# 51_VO-HDMI2_0_TX_DP_to_HDMI.net
KiCad netlist of a schematic drawn in Altium Designer
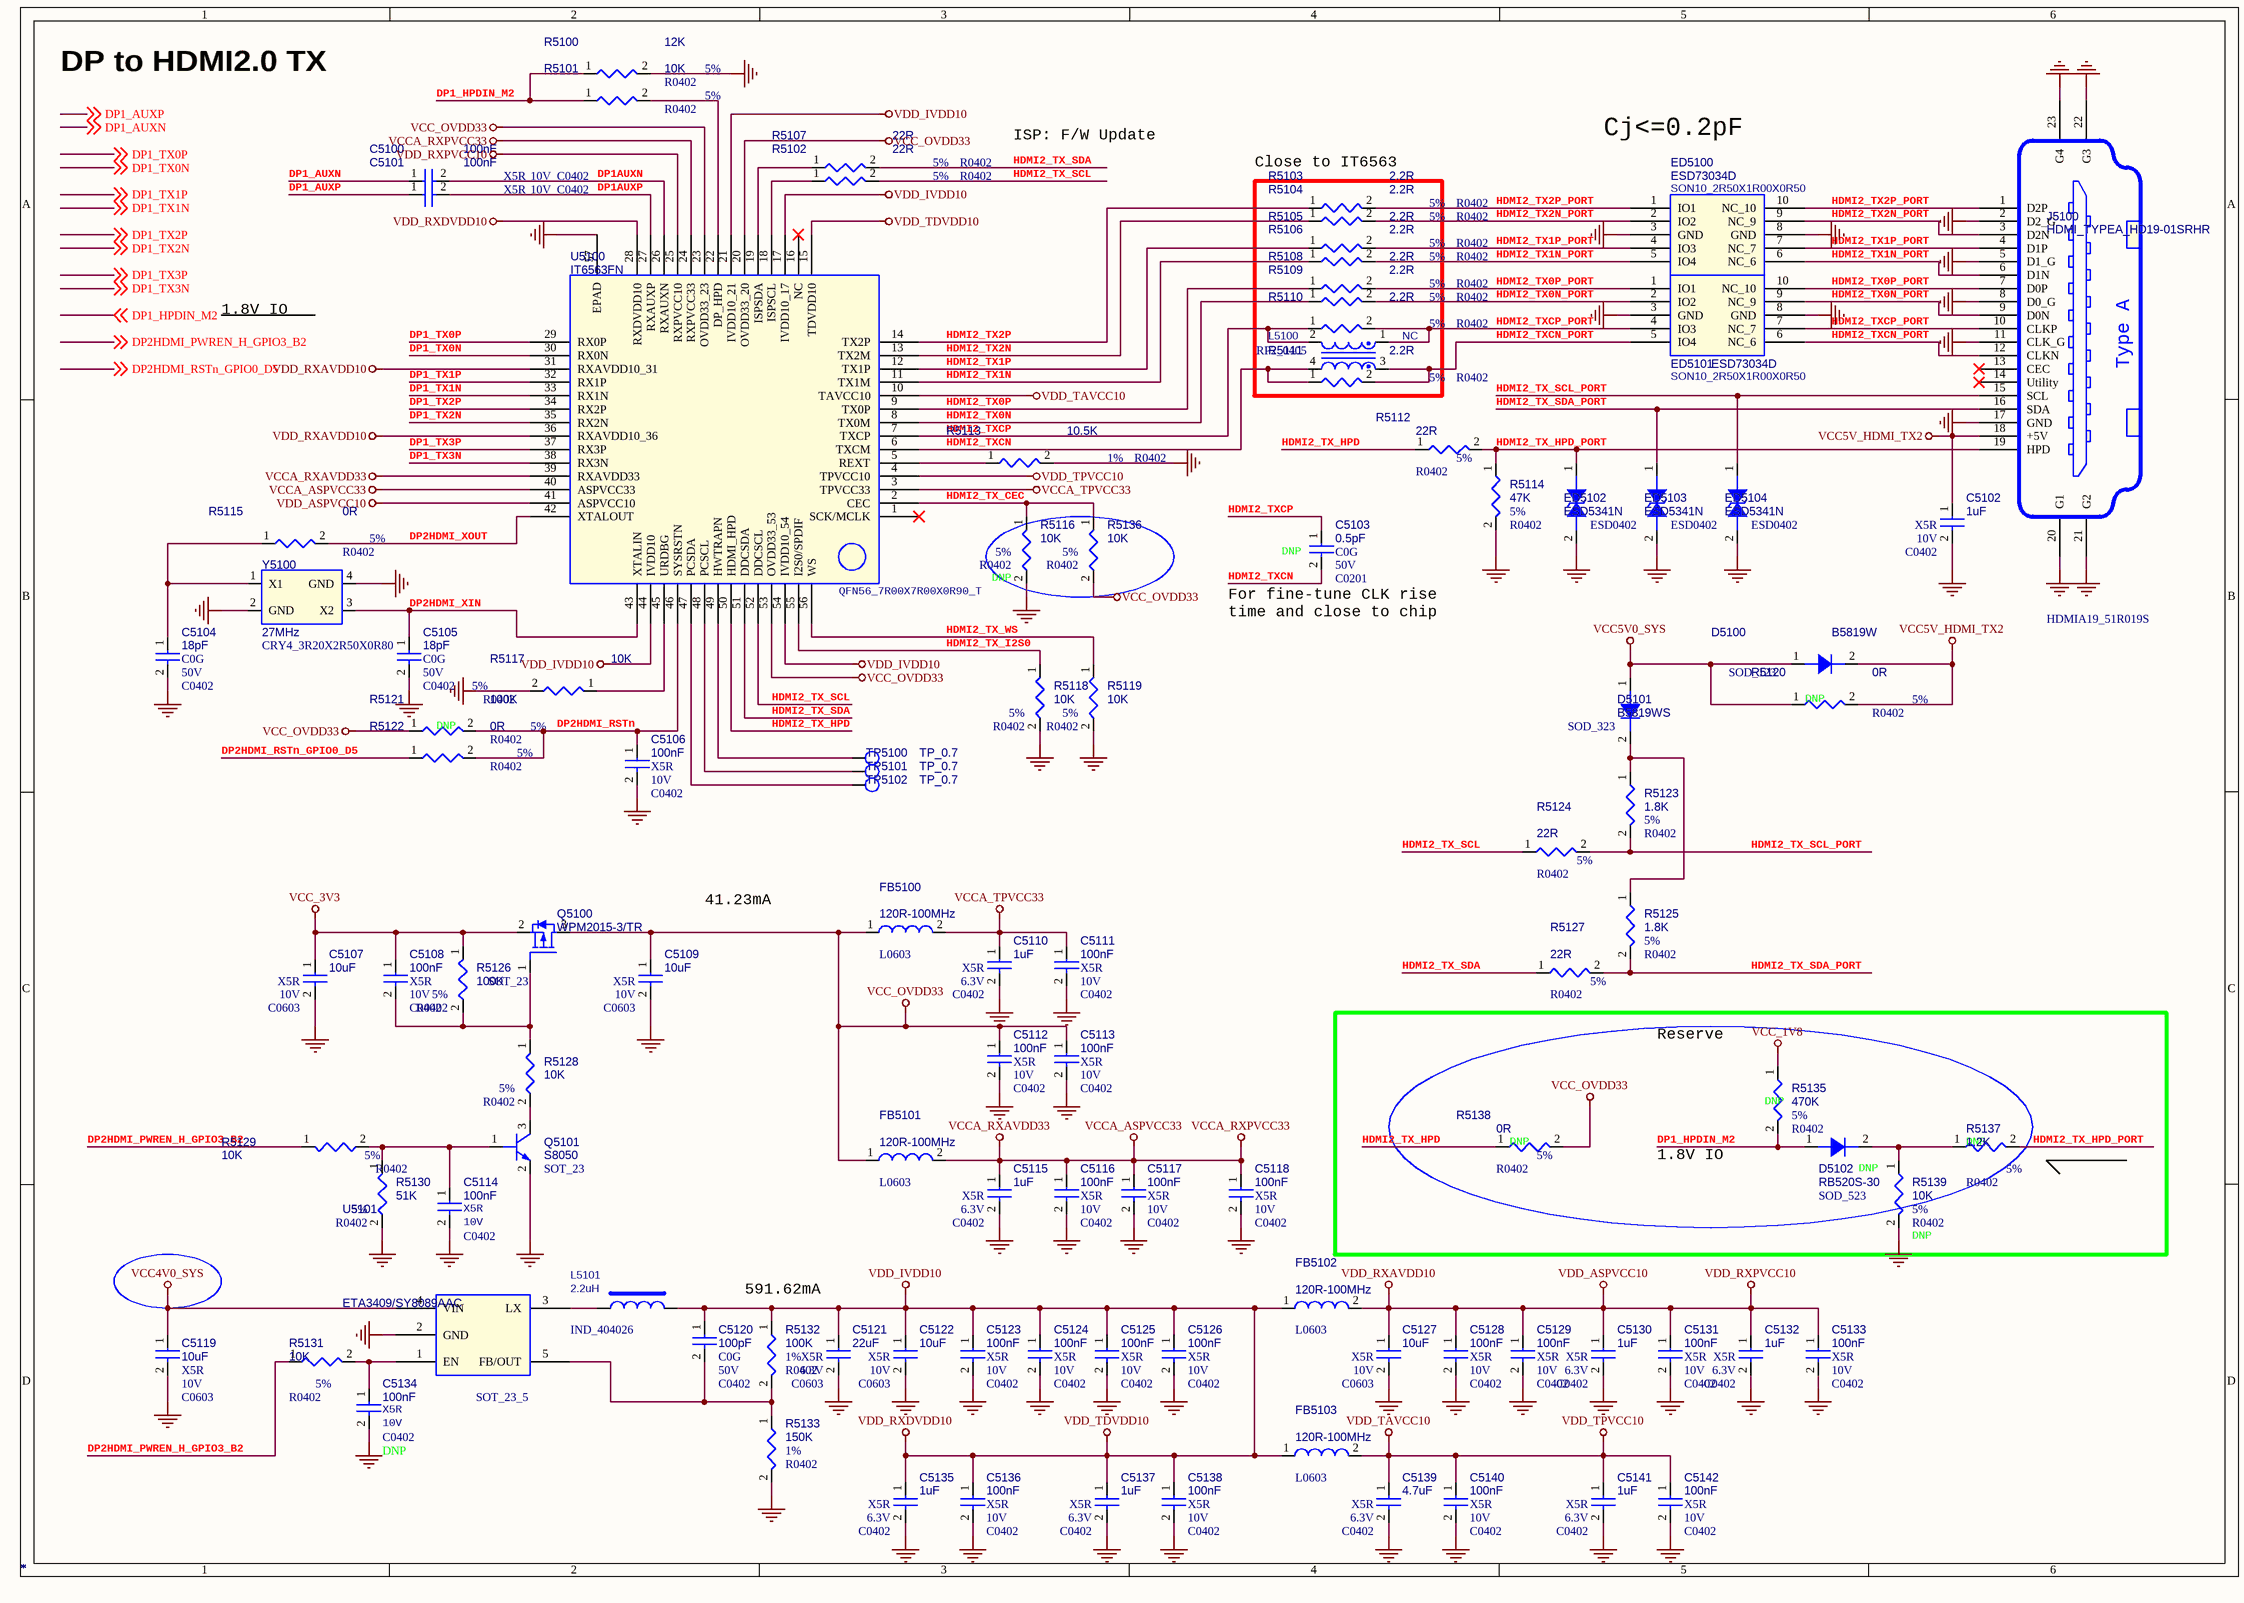
[diagram p0: 51.VO-HDMI2.0 TX(DP to HDMI).SchDoc]

(export (version "E")
  (design (tool "Eeschema 10.0.6"))
  (components
    (comp (ref "C5100")
      (value "*")
      (footprint "C0402")
      (description "cap,100.00nF,+/-10%,10V,X5R,C0402")
      (fields
        (field (name "VOLTAGE") "10V")
        (field (name "PCB FOOTPRINT") "C0402")
        (field (name "DIELECTRIC") "X5R")
        (field (name "TOLERANCE") "10%")
        (field (name "MANUFACTURER") "TDK")
        (field (name "ALTIUM_UNNAMED_1") "100nF")
        (field (name "CREATED BY") "JJJ")
      )
      (libsource (lib "*") (part "CAP NP"))
    )
    (comp (ref "C5101")
      (value "*")
      (footprint "C0402")
      (description "cap,100.00nF,+/-10%,10V,X5R,C0402")
      (fields
        (field (name "VOLTAGE") "10V")
        (field (name "PCB FOOTPRINT") "C0402")
        (field (name "DIELECTRIC") "X5R")
        (field (name "MANUFACTURER") "TDK")
        (field (name "TOLERANCE") "10%")
        (field (name "ALTIUM_UNNAMED_1") "100nF")
        (field (name "CREATED BY") "JJJ")
      )
      (libsource (lib "*") (part "CAP NP"))
    )
    (comp (ref "C5102")
      (value "*")
      (footprint "C0402")
      (description "cap,1.00uF,+/-10%,10V,X5R,C0402")
      (fields
        (field (name "VOLTAGE") "10V")
        (field (name "PCB FOOTPRINT") "C0402")
        (field (name "DIELECTRIC") "X5R")
        (field (name "MANUFACTURER") "TDK")
        (field (name "TOLERANCE") "10%")
        (field (name "ALTIUM_UNNAMED_1") "1uF")
        (field (name "CREATED BY") "JJJ")
      )
      (libsource (lib "*") (part "CAP NP"))
    )
    (comp (ref "C5103")
      (value "*")
      (footprint "C0201")
      (description "cap,0.50pF,+/-0.25,50V,C0G,C0201")
      (fields
        (field (name "VOLTAGE") "50V")
        (field (name "PCB FOOTPRINT") "C0201")
        (field (name "DIELECTRIC") "C0G")
        (field (name "OPTION") "DNP")
        (field (name "TOLERANCE") "+/-0.25pF")
        (field (name "MANUFACTURER") "TDK")
        (field (name "ALTIUM_UNNAMED_1") "0.5pF")
        (field (name "CREATED BY") "JJJ")
      )
      (libsource (lib "*") (part "CAP NP"))
    )
    (comp (ref "C5104")
      (value "*")
      (footprint "C0402")
      (description "cap,18.00pF,+/-5%,50V,C0G,C0402")
      (fields
        (field (name "VOLTAGE") "50V")
        (field (name "PCB FOOTPRINT") "C0402")
        (field (name "DIELECTRIC") "C0G")
        (field (name "MANUFACTURER") "TDK")
        (field (name "TOLERANCE") "5%")
        (field (name "ALTIUM_UNNAMED_1") "18pF")
        (field (name "CREATED BY") "JJJ")
      )
      (libsource (lib "*") (part "CAP NP"))
    )
    (comp (ref "C5105")
      (value "*")
      (footprint "C0402")
      (description "cap,18.00pF,+/-5%,50V,C0G,C0402")
      (fields
        (field (name "VOLTAGE") "50V")
        (field (name "PCB FOOTPRINT") "C0402")
        (field (name "DIELECTRIC") "C0G")
        (field (name "MANUFACTURER") "TDK")
        (field (name "TOLERANCE") "5%")
        (field (name "ALTIUM_UNNAMED_1") "18pF")
        (field (name "CREATED BY") "JJJ")
      )
      (libsource (lib "*") (part "CAP NP"))
    )
    (comp (ref "C5106")
      (value "*")
      (footprint "C0402")
      (description "cap,100.00nF,+/-10%,10V,X5R,C0402")
      (fields
        (field (name "VOLTAGE") "10V")
        (field (name "PCB FOOTPRINT") "C0402")
        (field (name "DIELECTRIC") "X5R")
        (field (name "MANUFACTURER") "TDK")
        (field (name "TOLERANCE") "10%")
        (field (name "ALTIUM_UNNAMED_1") "100nF")
        (field (name "CREATED BY") "JJJ")
      )
      (libsource (lib "*") (part "CAP NP"))
    )
    (comp (ref "C5107")
      (value "*")
      (footprint "C0603")
      (description "cap,10.00uF,+/-10%,10V,X5R,C0603")
      (fields
        (field (name "VOLTAGE") "10V")
        (field (name "PCB FOOTPRINT") "C0603")
        (field (name "DIELECTRIC") "X5R")
        (field (name "MANUFACTURER") "TDK")
        (field (name "TOLERANCE") "10%")
        (field (name "ALTIUM_UNNAMED_1") "10uF")
        (field (name "CREATED BY") "JJJ")
      )
      (libsource (lib "*") (part "CAP NP"))
    )
    (comp (ref "C5108")
      (value "*")
      (footprint "C0402")
      (description "cap,100.00nF,+/-10%,10V,X5R,C0402")
      (fields
        (field (name "VOLTAGE") "10V")
        (field (name "PCB FOOTPRINT") "C0402")
        (field (name "DIELECTRIC") "X5R")
        (field (name "TOLERANCE") "10%")
        (field (name "MANUFACTURER") "TDK")
        (field (name "ALTIUM_UNNAMED_1") "100nF")
        (field (name "CREATED BY") "JJJ")
      )
      (libsource (lib "*") (part "CAP NP"))
    )
    (comp (ref "C5109")
      (value "*")
      (footprint "C0603")
      (description "cap,10.00uF,+/-10%,10V,X5R,C0603")
      (fields
        (field (name "VOLTAGE") "10V")
        (field (name "PCB FOOTPRINT") "C0603")
        (field (name "DIELECTRIC") "X5R")
        (field (name "MANUFACTURER") "TDK")
        (field (name "TOLERANCE") "10%")
        (field (name "ALTIUM_UNNAMED_1") "10uF")
        (field (name "CREATED BY") "JJJ")
      )
      (libsource (lib "*") (part "CAP NP"))
    )
    (comp (ref "C5110")
      (value "*")
      (footprint "C0402")
      (description "cap,1.00uF,+/-10%,6.3V,X5R,C0402")
      (fields
        (field (name "VOLTAGE") "6.3V")
        (field (name "PCB FOOTPRINT") "C0402")
        (field (name "DIELECTRIC") "X5R")
        (field (name "TOLERANCE") "10%")
        (field (name "MANUFACTURER") "TDK")
        (field (name "ALTIUM_UNNAMED_1") "1uF")
        (field (name "CREATED BY") "JJJ")
      )
      (libsource (lib "*") (part "CAP NP"))
    )
    (comp (ref "C5111")
      (value "*")
      (footprint "C0402")
      (description "cap,100.00nF,+/-10%,10V,X5R,C0402")
      (fields
        (field (name "VOLTAGE") "10V")
        (field (name "PCB FOOTPRINT") "C0402")
        (field (name "DIELECTRIC") "X5R")
        (field (name "TOLERANCE") "10%")
        (field (name "MANUFACTURER") "TDK")
        (field (name "ALTIUM_UNNAMED_1") "100nF")
        (field (name "CREATED BY") "JJJ")
      )
      (libsource (lib "*") (part "CAP NP"))
    )
    (comp (ref "C5112")
      (value "*")
      (footprint "C0402")
      (description "cap,100.00nF,+/-10%,10V,X5R,C0402")
      (fields
        (field (name "VOLTAGE") "10V")
        (field (name "PCB FOOTPRINT") "C0402")
        (field (name "DIELECTRIC") "X5R")
        (field (name "MANUFACTURER") "TDK")
        (field (name "TOLERANCE") "10%")
        (field (name "ALTIUM_UNNAMED_1") "100nF")
        (field (name "CREATED BY") "JJJ")
      )
      (libsource (lib "*") (part "CAP NP"))
    )
    (comp (ref "C5113")
      (value "*")
      (footprint "C0402")
      (description "cap,100.00nF,+/-10%,10V,X5R,C0402")
      (fields
        (field (name "VOLTAGE") "10V")
        (field (name "PCB FOOTPRINT") "C0402")
        (field (name "DIELECTRIC") "X5R")
        (field (name "MANUFACTURER") "TDK")
        (field (name "TOLERANCE") "10%")
        (field (name "ALTIUM_UNNAMED_1") "100nF")
        (field (name "CREATED BY") "JJJ")
      )
      (libsource (lib "*") (part "CAP NP"))
    )
    (comp (ref "C5114")
      (value "*")
      (footprint "C0402")
      (description "cap,100.00nF,+/-10%,10V,X5R,C0402")
      (fields
        (field (name "VOLTAGE") "10V")
        (field (name "PCB FOOTPRINT") "C0402")
        (field (name "DIELECTRIC") "X5R")
        (field (name "TOLERANCE") "10%")
        (field (name "MANUFACTURER") "TDK")
        (field (name "ALTIUM_UNNAMED_1") "100nF")
        (field (name "CREATED BY") "JJJ")
      )
      (libsource (lib "*") (part "CAP NP"))
    )
    (comp (ref "C5115")
      (value "*")
      (footprint "C0402")
      (description "cap,1.00uF,+/-10%,6.3V,X5R,C0402")
      (fields
        (field (name "VOLTAGE") "6.3V")
        (field (name "PCB FOOTPRINT") "C0402")
        (field (name "DIELECTRIC") "X5R")
        (field (name "TOLERANCE") "10%")
        (field (name "MANUFACTURER") "TDK")
        (field (name "ALTIUM_UNNAMED_1") "1uF")
        (field (name "CREATED BY") "JJJ")
      )
      (libsource (lib "*") (part "CAP NP"))
    )
    (comp (ref "C5116")
      (value "*")
      (footprint "C0402")
      (description "cap,100.00nF,+/-10%,10V,X5R,C0402")
      (fields
        (field (name "VOLTAGE") "10V")
        (field (name "PCB FOOTPRINT") "C0402")
        (field (name "DIELECTRIC") "X5R")
        (field (name "TOLERANCE") "10%")
        (field (name "MANUFACTURER") "TDK")
        (field (name "ALTIUM_UNNAMED_1") "100nF")
        (field (name "CREATED BY") "JJJ")
      )
      (libsource (lib "*") (part "CAP NP"))
    )
    (comp (ref "C5117")
      (value "*")
      (footprint "C0402")
      (description "cap,100.00nF,+/-10%,10V,X5R,C0402")
      (fields
        (field (name "VOLTAGE") "10V")
        (field (name "PCB FOOTPRINT") "C0402")
        (field (name "DIELECTRIC") "X5R")
        (field (name "MANUFACTURER") "TDK")
        (field (name "TOLERANCE") "10%")
        (field (name "ALTIUM_UNNAMED_1") "100nF")
        (field (name "CREATED BY") "JJJ")
      )
      (libsource (lib "*") (part "CAP NP"))
    )
    (comp (ref "C5118")
      (value "*")
      (footprint "C0402")
      (description "cap,100.00nF,+/-10%,10V,X5R,C0402")
      (fields
        (field (name "VOLTAGE") "10V")
        (field (name "PCB FOOTPRINT") "C0402")
        (field (name "DIELECTRIC") "X5R")
        (field (name "MANUFACTURER") "TDK")
        (field (name "TOLERANCE") "10%")
        (field (name "ALTIUM_UNNAMED_1") "100nF")
        (field (name "CREATED BY") "JJJ")
      )
      (libsource (lib "*") (part "CAP NP"))
    )
    (comp (ref "C5119")
      (value "*")
      (footprint "C0603")
      (description "cap,10.00uF,+/-10%,10V,X5R,C0603")
      (fields
        (field (name "VOLTAGE") "10V")
        (field (name "PCB FOOTPRINT") "C0603")
        (field (name "DIELECTRIC") "X5R")
        (field (name "TOLERANCE") "10%")
        (field (name "MANUFACTURER") "TDK")
        (field (name "ALTIUM_UNNAMED_1") "10uF")
        (field (name "CREATED BY") "JJJ")
      )
      (libsource (lib "*") (part "CAP NP"))
    )
    (comp (ref "C5120")
      (value "*")
      (footprint "C0402")
      (description "cap,100.00pF,+/-10%,50V,C0G,C0402")
      (fields
        (field (name "VOLTAGE") "50V")
        (field (name "PCB FOOTPRINT") "C0402")
        (field (name "DIELECTRIC") "C0G")
        (field (name "TOLERANCE") "10%")
        (field (name "MANUFACTURER") "TDK")
        (field (name "ALTIUM_UNNAMED_1") "100pF")
        (field (name "CREATED BY") "JJJ")
      )
      (libsource (lib "*") (part "CAP NP"))
    )
    (comp (ref "C5121")
      (value "*")
      (footprint "C0603")
      (description "cap,22.00uF,+/-20%,6.3V,X5R,C0603")
      (fields
        (field (name "VOLTAGE") "6.3V")
        (field (name "PCB FOOTPRINT") "C0603")
        (field (name "DIELECTRIC") "X5R")
        (field (name "TOLERANCE") "20%")
        (field (name "MANUFACTURER") "TDK")
        (field (name "ALTIUM_UNNAMED_1") "22uF")
        (field (name "CREATED BY") "JJJ")
      )
      (libsource (lib "*") (part "CAP NP"))
    )
    (comp (ref "C5122")
      (value "*")
      (footprint "C0603")
      (description "cap,10.00uF,+/-10%,10V,X5R,C0603")
      (fields
        (field (name "VOLTAGE") "10V")
        (field (name "PCB FOOTPRINT") "C0603")
        (field (name "DIELECTRIC") "X5R")
        (field (name "MANUFACTURER") "TDK")
        (field (name "TOLERANCE") "10%")
        (field (name "ALTIUM_UNNAMED_1") "10uF")
        (field (name "CREATED BY") "JJJ")
      )
      (libsource (lib "*") (part "CAP NP"))
    )
    (comp (ref "C5123")
      (value "*")
      (footprint "C0402")
      (description "cap,100.00nF,+/-10%,10V,X5R,C0402")
      (fields
        (field (name "VOLTAGE") "10V")
        (field (name "PCB FOOTPRINT") "C0402")
        (field (name "DIELECTRIC") "X5R")
        (field (name "MANUFACTURER") "TDK")
        (field (name "TOLERANCE") "10%")
        (field (name "ALTIUM_UNNAMED_1") "100nF")
        (field (name "CREATED BY") "JJJ")
      )
      (libsource (lib "*") (part "CAP NP"))
    )
    (comp (ref "C5124")
      (value "*")
      (footprint "C0402")
      (description "cap,100.00nF,+/-10%,10V,X5R,C0402")
      (fields
        (field (name "VOLTAGE") "10V")
        (field (name "PCB FOOTPRINT") "C0402")
        (field (name "DIELECTRIC") "X5R")
        (field (name "MANUFACTURER") "TDK")
        (field (name "TOLERANCE") "10%")
        (field (name "ALTIUM_UNNAMED_1") "100nF")
        (field (name "CREATED BY") "JJJ")
      )
      (libsource (lib "*") (part "CAP NP"))
    )
    (comp (ref "C5125")
      (value "*")
      (footprint "C0402")
      (description "cap,100.00nF,+/-10%,10V,X5R,C0402")
      (fields
        (field (name "VOLTAGE") "10V")
        (field (name "PCB FOOTPRINT") "C0402")
        (field (name "DIELECTRIC") "X5R")
        (field (name "TOLERANCE") "10%")
        (field (name "MANUFACTURER") "TDK")
        (field (name "ALTIUM_UNNAMED_1") "100nF")
        (field (name "CREATED BY") "JJJ")
      )
      (libsource (lib "*") (part "CAP NP"))
    )
    (comp (ref "C5126")
      (value "*")
      (footprint "C0402")
      (description "cap,100.00nF,+/-10%,10V,X5R,C0402")
      (fields
        (field (name "VOLTAGE") "10V")
        (field (name "PCB FOOTPRINT") "C0402")
        (field (name "DIELECTRIC") "X5R")
        (field (name "MANUFACTURER") "TDK")
        (field (name "TOLERANCE") "10%")
        (field (name "ALTIUM_UNNAMED_1") "100nF")
        (field (name "CREATED BY") "JJJ")
      )
      (libsource (lib "*") (part "CAP NP"))
    )
    (comp (ref "C5127")
      (value "*")
      (footprint "C0603")
      (description "cap,10.00uF,+/-10%,10V,X5R,C0603")
      (fields
        (field (name "VOLTAGE") "10V")
        (field (name "PCB FOOTPRINT") "C0603")
        (field (name "DIELECTRIC") "X5R")
        (field (name "MANUFACTURER") "TDK")
        (field (name "TOLERANCE") "10%")
        (field (name "ALTIUM_UNNAMED_1") "10uF")
        (field (name "CREATED BY") "JJJ")
      )
      (libsource (lib "*") (part "CAP NP"))
    )
    (comp (ref "C5128")
      (value "*")
      (footprint "C0402")
      (description "cap,100.00nF,+/-10%,10V,X5R,C0402")
      (fields
        (field (name "VOLTAGE") "10V")
        (field (name "PCB FOOTPRINT") "C0402")
        (field (name "DIELECTRIC") "X5R")
        (field (name "TOLERANCE") "10%")
        (field (name "MANUFACTURER") "TDK")
        (field (name "ALTIUM_UNNAMED_1") "100nF")
        (field (name "CREATED BY") "JJJ")
      )
      (libsource (lib "*") (part "CAP NP"))
    )
    (comp (ref "C5129")
      (value "*")
      (footprint "C0402")
      (description "cap,100.00nF,+/-10%,10V,X5R,C0402")
      (fields
        (field (name "VOLTAGE") "10V")
        (field (name "PCB FOOTPRINT") "C0402")
        (field (name "DIELECTRIC") "X5R")
        (field (name "MANUFACTURER") "TDK")
        (field (name "TOLERANCE") "10%")
        (field (name "ALTIUM_UNNAMED_1") "100nF")
        (field (name "CREATED BY") "JJJ")
      )
      (libsource (lib "*") (part "CAP NP"))
    )
    (comp (ref "C5130")
      (value "*")
      (footprint "C0402")
      (description "cap,1.00uF,+/-10%,6.3V,X5R,C0402")
      (fields
        (field (name "VOLTAGE") "6.3V")
        (field (name "PCB FOOTPRINT") "C0402")
        (field (name "DIELECTRIC") "X5R")
        (field (name "TOLERANCE") "10%")
        (field (name "MANUFACTURER") "TDK")
        (field (name "ALTIUM_UNNAMED_1") "1uF")
        (field (name "CREATED BY") "JJJ")
      )
      (libsource (lib "*") (part "CAP NP"))
    )
    (comp (ref "C5131")
      (value "*")
      (footprint "C0402")
      (description "cap,100.00nF,+/-10%,10V,X5R,C0402")
      (fields
        (field (name "VOLTAGE") "10V")
        (field (name "PCB FOOTPRINT") "C0402")
        (field (name "DIELECTRIC") "X5R")
        (field (name "TOLERANCE") "10%")
        (field (name "MANUFACTURER") "TDK")
        (field (name "ALTIUM_UNNAMED_1") "100nF")
        (field (name "CREATED BY") "JJJ")
      )
      (libsource (lib "*") (part "CAP NP"))
    )
    (comp (ref "C5132")
      (value "*")
      (footprint "C0402")
      (description "cap,1.00uF,+/-10%,6.3V,X5R,C0402")
      (fields
        (field (name "VOLTAGE") "6.3V")
        (field (name "PCB FOOTPRINT") "C0402")
        (field (name "DIELECTRIC") "X5R")
        (field (name "TOLERANCE") "10%")
        (field (name "MANUFACTURER") "TDK")
        (field (name "ALTIUM_UNNAMED_1") "1uF")
        (field (name "CREATED BY") "JJJ")
      )
      (libsource (lib "*") (part "CAP NP"))
    )
    (comp (ref "C5133")
      (value "*")
      (footprint "C0402")
      (description "cap,100.00nF,+/-10%,10V,X5R,C0402")
      (fields
        (field (name "VOLTAGE") "10V")
        (field (name "PCB FOOTPRINT") "C0402")
        (field (name "DIELECTRIC") "X5R")
        (field (name "TOLERANCE") "10%")
        (field (name "MANUFACTURER") "TDK")
        (field (name "ALTIUM_UNNAMED_1") "100nF")
        (field (name "CREATED BY") "JJJ")
      )
      (libsource (lib "*") (part "CAP NP"))
    )
    (comp (ref "C5134")
      (value "*")
      (footprint "C0402")
      (description "cap,100.00nF,+/-10%,10V,X5R,C0402")
      (fields
        (field (name "VOLTAGE") "10V")
        (field (name "PCB FOOTPRINT") "C0402")
        (field (name "DIELECTRIC") "X5R")
        (field (name "TOLERANCE") "10%")
        (field (name "MANUFACTURER") "TDK")
        (field (name "OPTION") "DNP")
        (field (name "ALTIUM_UNNAMED_1") "100nF")
        (field (name "CREATED BY") "JJJ")
      )
      (libsource (lib "*") (part "CAP NP"))
    )
    (comp (ref "C5135")
      (value "*")
      (footprint "C0402")
      (description "cap,1.00uF,+/-10%,6.3V,X5R,C0402")
      (fields
        (field (name "VOLTAGE") "6.3V")
        (field (name "PCB FOOTPRINT") "C0402")
        (field (name "DIELECTRIC") "X5R")
        (field (name "MANUFACTURER") "TDK")
        (field (name "TOLERANCE") "10%")
        (field (name "ALTIUM_UNNAMED_1") "1uF")
        (field (name "CREATED BY") "JJJ")
      )
      (libsource (lib "*") (part "CAP NP"))
    )
    (comp (ref "C5136")
      (value "*")
      (footprint "C0402")
      (description "cap,100.00nF,+/-10%,10V,X5R,C0402")
      (fields
        (field (name "VOLTAGE") "10V")
        (field (name "PCB FOOTPRINT") "C0402")
        (field (name "DIELECTRIC") "X5R")
        (field (name "MANUFACTURER") "TDK")
        (field (name "TOLERANCE") "10%")
        (field (name "ALTIUM_UNNAMED_1") "100nF")
        (field (name "CREATED BY") "JJJ")
      )
      (libsource (lib "*") (part "CAP NP"))
    )
    (comp (ref "C5137")
      (value "*")
      (footprint "C0402")
      (description "cap,1.00uF,+/-10%,6.3V,X5R,C0402")
      (fields
        (field (name "VOLTAGE") "6.3V")
        (field (name "PCB FOOTPRINT") "C0402")
        (field (name "DIELECTRIC") "X5R")
        (field (name "TOLERANCE") "10%")
        (field (name "MANUFACTURER") "TDK")
        (field (name "ALTIUM_UNNAMED_1") "1uF")
        (field (name "CREATED BY") "JJJ")
      )
      (libsource (lib "*") (part "CAP NP"))
    )
    (comp (ref "C5138")
      (value "*")
      (footprint "C0402")
      (description "cap,100.00nF,+/-10%,10V,X5R,C0402")
      (fields
        (field (name "VOLTAGE") "10V")
        (field (name "PCB FOOTPRINT") "C0402")
        (field (name "DIELECTRIC") "X5R")
        (field (name "TOLERANCE") "10%")
        (field (name "MANUFACTURER") "TDK")
        (field (name "ALTIUM_UNNAMED_1") "100nF")
        (field (name "CREATED BY") "JJJ")
      )
      (libsource (lib "*") (part "CAP NP"))
    )
    (comp (ref "C5139")
      (value "*")
      (footprint "C0402")
      (description "cap,4.70uF,+/-10%,6.3V,X5R,C0402")
      (fields
        (field (name "VOLTAGE") "6.3V")
        (field (name "PCB FOOTPRINT") "C0402")
        (field (name "DIELECTRIC") "X5R")
        (field (name "TOLERANCE") "10%")
        (field (name "MANUFACTURER") "TDK")
        (field (name "ALTIUM_UNNAMED_1") "4.7uF")
        (field (name "CREATED BY") "JJJ")
      )
      (libsource (lib "*") (part "CAP NP"))
    )
    (comp (ref "C5140")
      (value "*")
      (footprint "C0402")
      (description "cap,100.00nF,+/-10%,10V,X5R,C0402")
      (fields
        (field (name "VOLTAGE") "10V")
        (field (name "PCB FOOTPRINT") "C0402")
        (field (name "DIELECTRIC") "X5R")
        (field (name "TOLERANCE") "10%")
        (field (name "MANUFACTURER") "TDK")
        (field (name "ALTIUM_UNNAMED_1") "100nF")
        (field (name "CREATED BY") "JJJ")
      )
      (libsource (lib "*") (part "CAP NP"))
    )
    (comp (ref "C5141")
      (value "*")
      (footprint "C0402")
      (description "cap,1.00uF,+/-10%,6.3V,X5R,C0402")
      (fields
        (field (name "VOLTAGE") "6.3V")
        (field (name "PCB FOOTPRINT") "C0402")
        (field (name "DIELECTRIC") "X5R")
        (field (name "TOLERANCE") "10%")
        (field (name "MANUFACTURER") "TDK")
        (field (name "ALTIUM_UNNAMED_1") "1uF")
        (field (name "CREATED BY") "JJJ")
      )
      (libsource (lib "*") (part "CAP NP"))
    )
    (comp (ref "C5142")
      (value "*")
      (footprint "C0402")
      (description "cap,100.00nF,+/-10%,10V,X5R,C0402")
      (fields
        (field (name "VOLTAGE") "10V")
        (field (name "PCB FOOTPRINT") "C0402")
        (field (name "DIELECTRIC") "X5R")
        (field (name "TOLERANCE") "10%")
        (field (name "MANUFACTURER") "TDK")
        (field (name "ALTIUM_UNNAMED_1") "100nF")
        (field (name "CREATED BY") "JJJ")
      )
      (libsource (lib "*") (part "CAP NP"))
    )
    (comp (ref "D5100")
      (value "*")
      (footprint "SOD_123")
      (description "Schottky BarrierЈ¬B5819W SOD-123")
      (fields
        (field (name "PCB FOOTPRINT") "SOD_123")
        (field (name "MANUFACTURER") "і¤µз")
        (field (name "ALTIUM_UNNAMED_1") "B5819W")
        (field (name "CREATED BY") "JJJ")
      )
      (libsource (lib "*") (part "DIODE"))
    )
    (comp (ref "D5101")
      (value "*")
      (footprint "SOD_323")
      (description "Schottky BarrierЈ¬B5819WS SOD-323")
      (fields
        (field (name "PCB FOOTPRINT") "SOD_323")
        (field (name "MANUFACTURER") "і¤µз")
        (field (name "ALTIUM_UNNAMED_1") "B5819WS")
        (field (name "CREATED BY") "JJJ")
      )
      (libsource (lib "*") (part "DIODE"))
    )
    (comp (ref "D5102")
      (value "*")
      (footprint "SOD_523")
      (description "Schottky barrier Diode")
      (fields
        (field (name "PCB FOOTPRINT") "SOD_523")
        (field (name "OPTION") "DNP")
        (field (name "MANUFACTURER") "і¤µз")
        (field (name "ALTIUM_UNNAMED_1") "RB520S-30")
        (field (name "CREATED BY") "JJJ")
      )
      (libsource (lib "*") (part "DIODE"))
    )
    (comp (ref "ED5100")
      (value "*")
      (footprint "SON10_2R50X1R00X0R50")
      (description "4-Lines, Uni-directional, Ultra-low Capacitance Transient Voltage Suppressors")
      (fields
        (field (name "PCB FOOTPRINT") "SON10_2R50X1R00X0R50")
        (field (name "MANUFACTURER") "WillSemi(О¤¶ы°лµјМе)")
        (field (name "ALTIUM_UNNAMED_1") "ESD73034D")
        (field (name "CREATED BY") "JJJ")
      )
      (libsource (lib "*") (part "ESD_ESD5304D"))
    )
    (comp (ref "ED5101")
      (value "*")
      (footprint "SON10_2R50X1R00X0R50")
      (description "4-Lines, Uni-directional, Ultra-low Capacitance Transient Voltage Suppressors")
      (fields
        (field (name "PCB FOOTPRINT") "SON10_2R50X1R00X0R50")
        (field (name "MANUFACTURER") "WillSemi(О¤¶ы°лµјМе)")
        (field (name "ALTIUM_UNNAMED_1") "ESD73034D")
        (field (name "CREATED BY") "JJJ")
      )
      (libsource (lib "*") (part "ESD_ESD5304D"))
    )
    (comp (ref "ED5102")
      (value "*")
      (footprint "ESD0402")
      (description "1-Line, Bi-directional, Transient Voltage Suppressors.1pF.")
      (fields
        (field (name "PCB FOOTPRINT") "ESD0402")
        (field (name "MANUFACTURER") "WillSemi(О¤¶ы°лµјМе)")
        (field (name "ALTIUM_UNNAMED_1") "ESD5341N")
        (field (name "CREATED BY") "JJJ")
      )
      (libsource (lib "*") (part "DIODE BI_DIR TRIG"))
    )
    (comp (ref "ED5103")
      (value "*")
      (footprint "ESD0402")
      (description "1-Line, Bi-directional, Transient Voltage Suppressors.1pF.")
      (fields
        (field (name "PCB FOOTPRINT") "ESD0402")
        (field (name "MANUFACTURER") "WillSemi(О¤¶ы°лµјМе)")
        (field (name "ALTIUM_UNNAMED_1") "ESD5341N")
        (field (name "CREATED BY") "JJJ")
      )
      (libsource (lib "*") (part "DIODE BI_DIR TRIG"))
    )
    (comp (ref "ED5104")
      (value "*")
      (footprint "ESD0402")
      (description "1-Line, Bi-directional, Transient Voltage Suppressors.1pF.")
      (fields
        (field (name "PCB FOOTPRINT") "ESD0402")
        (field (name "MANUFACTURER") "WillSemi(О¤¶ы°лµјМе)")
        (field (name "ALTIUM_UNNAMED_1") "ESD5341N")
        (field (name "CREATED BY") "JJJ")
      )
      (libsource (lib "*") (part "DIODE BI_DIR TRIG"))
    )
    (comp (ref "FB5100")
      (value "*")
      (footprint "L0603")
      (description "BEAD,120R@100MHz,current=2000mA,0603")
      (fields
        (field (name "TOLERANCE") "25%")
        (field (name "PCB FOOTPRINT") "L0603")
        (field (name "MANUFACTURER") "Murata")
        (field (name "ALTIUM_UNNAMED_1") "120R-100MHz")
        (field (name "CREATED BY") "DZS")
      )
      (libsource (lib "*") (part "BEAD"))
    )
    (comp (ref "FB5101")
      (value "*")
      (footprint "L0603")
      (description "BEAD,120R@100MHz,current=2000mA,0603")
      (fields
        (field (name "TOLERANCE") "25%")
        (field (name "PCB FOOTPRINT") "L0603")
        (field (name "MANUFACTURER") "Murata")
        (field (name "ALTIUM_UNNAMED_1") "120R-100MHz")
        (field (name "CREATED BY") "DZS")
      )
      (libsource (lib "*") (part "BEAD"))
    )
    (comp (ref "FB5102")
      (value "*")
      (footprint "L0603")
      (description "BEAD,120R@100MHz,current=2000mA,0603")
      (fields
        (field (name "TOLERANCE") "25%")
        (field (name "PCB FOOTPRINT") "L0603")
        (field (name "MANUFACTURER") "Murata")
        (field (name "ALTIUM_UNNAMED_1") "120R-100MHz")
        (field (name "CREATED BY") "DZS")
      )
      (libsource (lib "*") (part "BEAD"))
    )
    (comp (ref "FB5103")
      (value "*")
      (footprint "L0603")
      (description "BEAD,120R@100MHz,current=2000mA,0603")
      (fields
        (field (name "TOLERANCE") "25%")
        (field (name "PCB FOOTPRINT") "L0603")
        (field (name "MANUFACTURER") "Murata")
        (field (name "ALTIUM_UNNAMED_1") "120R-100MHz")
        (field (name "CREATED BY") "DZS")
      )
      (libsource (lib "*") (part "BEAD"))
    )
    (comp (ref "J5100")
      (value "*")
      (footprint "HDMIA19_51R019S")
      (fields
        (field (name "PCB FOOTPRINT") "HDMIA19_51R019S")
        (field (name "ALTIUM_UNNAMED_1") "HDMI_TYPEA_HD19-01SRHR")
      )
      (libsource (lib "*") (part "HDMI_TYPE_A_0"))
    )
    (comp (ref "L5100")
      (value "*")
      (footprint "L0402D")
      (description "Winding Type Common Mode Choke Coil")
      (fields
        (field (name "PCB FOOTPRINT") "RP2_0405")
        (field (name "TOLERANCE") "25%")
        (field (name "MANUFACTURER") "sunlord")
        (field (name "ALTIUM_UNNAMED_1") "NC")
        (field (name "CREATED BY") "JJJ")
      )
      (libsource (lib "*") (part "INDUCTOR COM"))
    )
    (comp (ref "L5101")
      (value "*")
      (footprint "IND_404026")
      (description "Power Inductor,2.2uH,0.2,IND_404026")
      (fields
        (field (name "PCB FOOTPRINT") "IND_404026")
        (field (name "MANUFACTURER") "sunlord")
        (field (name "TOLERANCE") "20%")
        (field (name "ALTIUM_UNNAMED_1") "2.2uH")
        (field (name "CREATED BY") "YTL")
      )
      (libsource (lib "*") (part "INDUCTORS OF FERRITE_Dup1"))
    )
    (comp (ref "Q5100")
      (value "*")
      (footprint "SOT23")
      (description "PMOS,WPM2015-3/TR,SOT_23,Id=2.4A,Vds=20V")
      (fields
        (field (name "PCB FOOTPRINT") "SOT_23")
        (field (name "MANUFACTURER") "WillSemi(О¤¶ы°лµјМе)")
        (field (name "ALTIUM_UNNAMED_1") "WPM2015-3/TR")
        (field (name "CREATED BY") "JJJ")
      )
      (libsource (lib "*") (part "MOSFET P"))
    )
    (comp (ref "Q5101")
      (value "*")
      (footprint "SOT_23")
      (description "S8050,SOT23")
      (fields
        (field (name "PCB FOOTPRINT") "SOT_23")
        (field (name "MANUFACTURER") "і¤µз")
        (field (name "ALTIUM_UNNAMED_1") "S8050")
        (field (name "CREATED BY") "JJJ")
      )
      (libsource (lib "*") (part "NPN"))
    )
    (comp (ref "R5100")
      (value "*")
      (footprint "R0402")
      (description "НЁУГєсД¤µзЧи,12K,+/-5%,R0402,1/16W.")
      (fields
        (field (name "PCB FOOTPRINT") "R0402")
        (field (name "TOLERANCE") "5%")
        (field (name "MANUFACTURER") "YAGEO")
        (field (name "ALTIUM_UNNAMED_1") "12K")
        (field (name "CREATED BY") "YTL")
      )
      (libsource (lib "*") (part "RESISTOR_Dup1"))
    )
    (comp (ref "R5101")
      (value "*")
      (footprint "R0402")
      (description "НЁУГєсД¤µзЧи,10K,+/-5%,R0402,1/16W.")
      (fields
        (field (name "PCB FOOTPRINT") "R0402")
        (field (name "TOLERANCE") "5%")
        (field (name "MANUFACTURER") "YAGEO")
        (field (name "ALTIUM_UNNAMED_1") "10K")
        (field (name "CREATED BY") "YTL")
      )
      (libsource (lib "*") (part "RESISTOR_Dup1"))
    )
    (comp (ref "R5102")
      (value "*")
      (footprint "R0402")
      (description "НЁУГєсД¤µзЧи,22R,+/-5%,R0402,1/16W.")
      (fields
        (field (name "PCB FOOTPRINT") "R0402")
        (field (name "TOLERANCE") "5%")
        (field (name "MANUFACTURER") "YAGEO")
        (field (name "ALTIUM_UNNAMED_1") "22R")
        (field (name "CREATED BY") "YTL")
      )
      (libsource (lib "*") (part "RESISTOR_Dup1"))
    )
    (comp (ref "R5103")
      (value "*")
      (footprint "R0402")
      (description "НЁУГєсД¤µзЧи,2R2,+/-5%,R0402,1/16W.")
      (fields
        (field (name "PCB FOOTPRINT") "R0402")
        (field (name "TOLERANCE") "5%")
        (field (name "MANUFACTURER") "YAGEO")
        (field (name "ALTIUM_UNNAMED_1") "2.2R")
        (field (name "CREATED BY") "YTL")
      )
      (libsource (lib "*") (part "RESISTOR_Dup1"))
    )
    (comp (ref "R5104")
      (value "*")
      (footprint "R0402")
      (description "НЁУГєсД¤µзЧи,2R2,+/-5%,R0402,1/16W.")
      (fields
        (field (name "PCB FOOTPRINT") "R0402")
        (field (name "TOLERANCE") "5%")
        (field (name "MANUFACTURER") "YAGEO")
        (field (name "ALTIUM_UNNAMED_1") "2.2R")
        (field (name "CREATED BY") "YTL")
      )
      (libsource (lib "*") (part "RESISTOR_Dup1"))
    )
    (comp (ref "R5105")
      (value "*")
      (footprint "R0402")
      (description "НЁУГєсД¤µзЧи,2R2,+/-5%,R0402,1/16W.")
      (fields
        (field (name "PCB FOOTPRINT") "R0402")
        (field (name "TOLERANCE") "5%")
        (field (name "MANUFACTURER") "YAGEO")
        (field (name "ALTIUM_UNNAMED_1") "2.2R")
        (field (name "CREATED BY") "YTL")
      )
      (libsource (lib "*") (part "RESISTOR_Dup1"))
    )
    (comp (ref "R5106")
      (value "*")
      (footprint "R0402")
      (description "НЁУГєсД¤µзЧи,2R2,+/-5%,R0402,1/16W.")
      (fields
        (field (name "PCB FOOTPRINT") "R0402")
        (field (name "TOLERANCE") "5%")
        (field (name "MANUFACTURER") "YAGEO")
        (field (name "ALTIUM_UNNAMED_1") "2.2R")
        (field (name "CREATED BY") "YTL")
      )
      (libsource (lib "*") (part "RESISTOR_Dup1"))
    )
    (comp (ref "R5107")
      (value "*")
      (footprint "R0402")
      (description "НЁУГєсД¤µзЧи,22R,+/-5%,R0402,1/16W.")
      (fields
        (field (name "PCB FOOTPRINT") "R0402")
        (field (name "TOLERANCE") "5%")
        (field (name "MANUFACTURER") "YAGEO")
        (field (name "ALTIUM_UNNAMED_1") "22R")
        (field (name "CREATED BY") "YTL")
      )
      (libsource (lib "*") (part "RESISTOR_Dup1"))
    )
    (comp (ref "R5108")
      (value "*")
      (footprint "R0402")
      (description "НЁУГєсД¤µзЧи,2R2,+/-5%,R0402,1/16W.")
      (fields
        (field (name "PCB FOOTPRINT") "R0402")
        (field (name "TOLERANCE") "5%")
        (field (name "MANUFACTURER") "YAGEO")
        (field (name "ALTIUM_UNNAMED_1") "2.2R")
        (field (name "CREATED BY") "YTL")
      )
      (libsource (lib "*") (part "RESISTOR_Dup1"))
    )
    (comp (ref "R5109")
      (value "*")
      (footprint "R0402")
      (description "НЁУГєсД¤µзЧи,2R2,+/-5%,R0402,1/16W.")
      (fields
        (field (name "PCB FOOTPRINT") "R0402")
        (field (name "TOLERANCE") "5%")
        (field (name "MANUFACTURER") "YAGEO")
        (field (name "ALTIUM_UNNAMED_1") "2.2R")
        (field (name "CREATED BY") "YTL")
      )
      (libsource (lib "*") (part "RESISTOR_Dup1"))
    )
    (comp (ref "R5110")
      (value "*")
      (footprint "R0402")
      (description "НЁУГєсД¤µзЧи,2R2,+/-5%,R0402,1/16W.")
      (fields
        (field (name "PCB FOOTPRINT") "R0402")
        (field (name "TOLERANCE") "5%")
        (field (name "MANUFACTURER") "YAGEO")
        (field (name "ALTIUM_UNNAMED_1") "2.2R")
        (field (name "CREATED BY") "YTL")
      )
      (libsource (lib "*") (part "RESISTOR_Dup1"))
    )
    (comp (ref "R5111")
      (value "*")
      (footprint "R0402")
      (description "НЁУГєсД¤µзЧи,2R2,+/-5%,R0402,1/16W.")
      (fields
        (field (name "PCB FOOTPRINT") "R0402")
        (field (name "TOLERANCE") "5%")
        (field (name "MANUFACTURER") "YAGEO")
        (field (name "ALTIUM_UNNAMED_1") "2.2R")
        (field (name "CREATED BY") "YTL")
      )
      (libsource (lib "*") (part "RESISTOR_Dup1"))
    )
    (comp (ref "R5112")
      (value "*")
      (footprint "R0402")
      (description "НЁУГєсД¤µзЧи,22R,+/-5%,R0402,1/16W.")
      (fields
        (field (name "PCB FOOTPRINT") "R0402")
        (field (name "TOLERANCE") "5%")
        (field (name "MANUFACTURER") "YAGEO")
        (field (name "ALTIUM_UNNAMED_1") "22R")
        (field (name "CREATED BY") "YTL")
      )
      (libsource (lib "*") (part "RESISTOR_Dup1"))
    )
    (comp (ref "R5113")
      (value "*")
      (footprint "R0402")
      (description "НЁУГєсД¤µзЧи,10K5,+/-1%,R0402,1/16W.")
      (fields
        (field (name "PCB FOOTPRINT") "R0402")
        (field (name "TOLERANCE") "1%")
        (field (name "MANUFACTURER") "YAGEO")
        (field (name "ALTIUM_UNNAMED_1") "10.5K")
        (field (name "CREATED BY") "YTL")
      )
      (libsource (lib "*") (part "RESISTOR_Dup1"))
    )
    (comp (ref "R5114")
      (value "*")
      (footprint "R0402")
      (description "НЁУГєсД¤µзЧи,47K,+/-5%,R0402,1/16W.")
      (fields
        (field (name "PCB FOOTPRINT") "R0402")
        (field (name "TOLERANCE") "5%")
        (field (name "MANUFACTURER") "YAGEO")
        (field (name "ALTIUM_UNNAMED_1") "47K")
        (field (name "CREATED BY") "YTL")
      )
      (libsource (lib "*") (part "RESISTOR_Dup1"))
    )
    (comp (ref "R5115")
      (value "*")
      (footprint "R0402")
      (description "НЁУГєсД¤µзЧи,0R,+/-5%,R0402,1/16W.")
      (fields
        (field (name "PCB FOOTPRINT") "R0402")
        (field (name "TOLERANCE") "5%")
        (field (name "MANUFACTURER") "YAGEO")
        (field (name "ALTIUM_UNNAMED_1") "0R")
        (field (name "CREATED BY") "YTL")
      )
      (libsource (lib "*") (part "RESISTOR_Dup1"))
    )
    (comp (ref "R5116")
      (value "*")
      (footprint "R0402")
      (description "НЁУГєсД¤µзЧи,10K,+/-5%,R0402,1/16W.")
      (fields
        (field (name "PCB FOOTPRINT") "R0402")
        (field (name "TOLERANCE") "5%")
        (field (name "MANUFACTURER") "YAGEO")
        (field (name "OPTION") "DNP")
        (field (name "ALTIUM_UNNAMED_1") "10K")
        (field (name "CREATED BY") "YTL")
      )
      (libsource (lib "*") (part "RESISTOR_Dup1"))
    )
    (comp (ref "R5117")
      (value "*")
      (footprint "R0402")
      (description "НЁУГєсД¤µзЧи,10K,+/-5%,R0402,1/16W.")
      (fields
        (field (name "PCB FOOTPRINT") "R0402")
        (field (name "TOLERANCE") "5%")
        (field (name "MANUFACTURER") "YAGEO")
        (field (name "ALTIUM_UNNAMED_1") "10K")
        (field (name "CREATED BY") "YTL")
      )
      (libsource (lib "*") (part "RESISTOR_Dup1"))
    )
    (comp (ref "R5118")
      (value "*")
      (footprint "R0402")
      (description "НЁУГєсД¤µзЧи,10K,+/-5%,R0402,1/16W.")
      (fields
        (field (name "PCB FOOTPRINT") "R0402")
        (field (name "TOLERANCE") "5%")
        (field (name "MANUFACTURER") "YAGEO")
        (field (name "ALTIUM_UNNAMED_1") "10K")
        (field (name "CREATED BY") "YTL")
      )
      (libsource (lib "*") (part "RESISTOR_Dup1"))
    )
    (comp (ref "R5119")
      (value "*")
      (footprint "R0402")
      (description "НЁУГєсД¤µзЧи,10K,+/-5%,R0402,1/16W.")
      (fields
        (field (name "PCB FOOTPRINT") "R0402")
        (field (name "TOLERANCE") "5%")
        (field (name "MANUFACTURER") "YAGEO")
        (field (name "ALTIUM_UNNAMED_1") "10K")
        (field (name "CREATED BY") "YTL")
      )
      (libsource (lib "*") (part "RESISTOR_Dup1"))
    )
    (comp (ref "R5120")
      (value "*")
      (footprint "R0402")
      (description "НЁУГєсД¤µзЧи,0R,+/-5%,R0402,1/16W.")
      (fields
        (field (name "PCB FOOTPRINT") "R0402")
        (field (name "TOLERANCE") "5%")
        (field (name "MANUFACTURER") "YAGEO")
        (field (name "OPTION") "DNP")
        (field (name "ALTIUM_UNNAMED_1") "0R")
        (field (name "CREATED BY") "YTL")
      )
      (libsource (lib "*") (part "RESISTOR_Dup1"))
    )
    (comp (ref "R5121")
      (value "*")
      (footprint "R0402")
      (description "НЁУГєсД¤µзЧи,100K,+/-5%,R0402,1/16W.")
      (fields
        (field (name "PCB FOOTPRINT") "R0402")
        (field (name "TOLERANCE") "5%")
        (field (name "MANUFACTURER") "YAGEO")
        (field (name "OPTION") "DNP")
        (field (name "ALTIUM_UNNAMED_1") "100K")
        (field (name "CREATED BY") "YTL")
      )
      (libsource (lib "*") (part "RESISTOR_Dup1"))
    )
    (comp (ref "R5122")
      (value "*")
      (footprint "R0402")
      (description "НЁУГєсД¤µзЧи,0R,+/-5%,R0402,1/16W.")
      (fields
        (field (name "PCB FOOTPRINT") "R0402")
        (field (name "TOLERANCE") "5%")
        (field (name "MANUFACTURER") "YAGEO")
        (field (name "ALTIUM_UNNAMED_1") "0R")
        (field (name "CREATED BY") "YTL")
      )
      (libsource (lib "*") (part "RESISTOR_Dup1"))
    )
    (comp (ref "R5123")
      (value "*")
      (footprint "R0402")
      (description "НЁУГєсД¤µзЧи,1K8,+/-5%,R0402,1/16W.")
      (fields
        (field (name "PCB FOOTPRINT") "R0402")
        (field (name "TOLERANCE") "5%")
        (field (name "MANUFACTURER") "YAGEO")
        (field (name "ALTIUM_UNNAMED_1") "1.8K")
        (field (name "CREATED BY") "YTL")
      )
      (libsource (lib "*") (part "RESISTOR_Dup1"))
    )
    (comp (ref "R5124")
      (value "*")
      (footprint "R0402")
      (description "НЁУГєсД¤µзЧи,22R,+/-5%,R0402,1/16W.")
      (fields
        (field (name "PCB FOOTPRINT") "R0402")
        (field (name "TOLERANCE") "5%")
        (field (name "MANUFACTURER") "YAGEO")
        (field (name "ALTIUM_UNNAMED_1") "22R")
        (field (name "CREATED BY") "YTL")
      )
      (libsource (lib "*") (part "RESISTOR_Dup1"))
    )
    (comp (ref "R5125")
      (value "*")
      (footprint "R0402")
      (description "НЁУГєсД¤µзЧи,1K8,+/-5%,R0402,1/16W.")
      (fields
        (field (name "PCB FOOTPRINT") "R0402")
        (field (name "TOLERANCE") "5%")
        (field (name "MANUFACTURER") "YAGEO")
        (field (name "ALTIUM_UNNAMED_1") "1.8K")
        (field (name "CREATED BY") "YTL")
      )
      (libsource (lib "*") (part "RESISTOR_Dup1"))
    )
    (comp (ref "R5126")
      (value "*")
      (footprint "R0402")
      (description "НЁУГєсД¤µзЧи,100K,+/-5%,R0402,1/16W.")
      (fields
        (field (name "PCB FOOTPRINT") "R0402")
        (field (name "TOLERANCE") "5%")
        (field (name "MANUFACTURER") "YAGEO")
        (field (name "ALTIUM_UNNAMED_1") "100K")
        (field (name "CREATED BY") "YTL")
      )
      (libsource (lib "*") (part "RESISTOR_Dup1"))
    )
    (comp (ref "R5127")
      (value "*")
      (footprint "R0402")
      (description "НЁУГєсД¤µзЧи,22R,+/-5%,R0402,1/16W.")
      (fields
        (field (name "PCB FOOTPRINT") "R0402")
        (field (name "TOLERANCE") "5%")
        (field (name "MANUFACTURER") "YAGEO")
        (field (name "ALTIUM_UNNAMED_1") "22R")
        (field (name "CREATED BY") "YTL")
      )
      (libsource (lib "*") (part "RESISTOR_Dup1"))
    )
    (comp (ref "R5128")
      (value "*")
      (footprint "R0402")
      (description "НЁУГєсД¤µзЧи,10K,+/-5%,R0402,1/16W.")
      (fields
        (field (name "PCB FOOTPRINT") "R0402")
        (field (name "TOLERANCE") "5%")
        (field (name "MANUFACTURER") "YAGEO")
        (field (name "ALTIUM_UNNAMED_1") "10K")
        (field (name "CREATED BY") "YTL")
      )
      (libsource (lib "*") (part "RESISTOR_Dup1"))
    )
    (comp (ref "R5129")
      (value "*")
      (footprint "R0402")
      (description "НЁУГєсД¤µзЧи,10K,+/-5%,R0402,1/16W.")
      (fields
        (field (name "PCB FOOTPRINT") "R0402")
        (field (name "TOLERANCE") "5%")
        (field (name "MANUFACTURER") "YAGEO")
        (field (name "ALTIUM_UNNAMED_1") "10K")
        (field (name "CREATED BY") "YTL")
      )
      (libsource (lib "*") (part "RESISTOR_Dup1"))
    )
    (comp (ref "R5130")
      (value "*")
      (footprint "R0402")
      (description "НЁУГєсД¤µзЧи,51K,+/-5%,R0402,1/16W.")
      (fields
        (field (name "PCB FOOTPRINT") "R0402")
        (field (name "TOLERANCE") "5%")
        (field (name "MANUFACTURER") "YAGEO")
        (field (name "ALTIUM_UNNAMED_1") "51K")
        (field (name "CREATED BY") "YTL")
      )
      (libsource (lib "*") (part "RESISTOR_Dup1"))
    )
    (comp (ref "R5131")
      (value "*")
      (footprint "R0402")
      (description "НЁУГєсД¤µзЧи,10K,+/-5%,R0402,1/16W.")
      (fields
        (field (name "PCB FOOTPRINT") "R0402")
        (field (name "TOLERANCE") "5%")
        (field (name "MANUFACTURER") "YAGEO")
        (field (name "ALTIUM_UNNAMED_1") "10K")
        (field (name "CREATED BY") "YTL")
      )
      (libsource (lib "*") (part "RESISTOR_Dup1"))
    )
    (comp (ref "R5132")
      (value "*")
      (footprint "R0402")
      (description "НЁУГєсД¤µзЧи,100K,+/-1%,R0402,1/16W.")
      (fields
        (field (name "PCB FOOTPRINT") "R0402")
        (field (name "TOLERANCE") "1%")
        (field (name "MANUFACTURER") "YAGEO")
        (field (name "ALTIUM_UNNAMED_1") "100K")
        (field (name "CREATED BY") "YTL")
      )
      (libsource (lib "*") (part "RESISTOR_Dup1"))
    )
    (comp (ref "R5133")
      (value "*")
      (footprint "R0402")
      (description "НЁУГєсД¤µзЧи,150K,+/-1%,R0402,1/16W.")
      (fields
        (field (name "PCB FOOTPRINT") "R0402")
        (field (name "TOLERANCE") "1%")
        (field (name "MANUFACTURER") "YAGEO")
        (field (name "ALTIUM_UNNAMED_1") "150K")
        (field (name "CREATED BY") "YTL")
      )
      (libsource (lib "*") (part "RESISTOR_Dup1"))
    )
    (comp (ref "R5135")
      (value "*")
      (footprint "R0402")
      (description "НЁУГєсД¤µзЧи,470K,+/-5%,R0402,1/16W.")
      (fields
        (field (name "PCB FOOTPRINT") "R0402")
        (field (name "TOLERANCE") "5%")
        (field (name "MANUFACTURER") "YAGEO")
        (field (name "OPTION") "DNP")
        (field (name "ALTIUM_UNNAMED_1") "470K")
        (field (name "CREATED BY") "YTL")
      )
      (libsource (lib "*") (part "RESISTOR_Dup1"))
    )
    (comp (ref "R5136")
      (value "*")
      (footprint "R0402")
      (description "НЁУГєсД¤µзЧи,10K,+/-5%,R0402,1/16W.")
      (fields
        (field (name "PCB FOOTPRINT") "R0402")
        (field (name "TOLERANCE") "5%")
        (field (name "MANUFACTURER") "YAGEO")
        (field (name "ALTIUM_UNNAMED_1") "10K")
        (field (name "CREATED BY") "YTL")
      )
      (libsource (lib "*") (part "RESISTOR_Dup1"))
    )
    (comp (ref "R5137")
      (value "*")
      (footprint "R0402")
      (description "НЁУГєсД¤µзЧи,1K2,+/-5%,R0402,1/16W.")
      (fields
        (field (name "PCB FOOTPRINT") "R0402")
        (field (name "TOLERANCE") "5%")
        (field (name "OPTION") "DNP")
        (field (name "MANUFACTURER") "YAGEO")
        (field (name "ALTIUM_UNNAMED_1") "1.2K")
        (field (name "CREATED BY") "YTL")
      )
      (libsource (lib "*") (part "RESISTOR_Dup1"))
    )
    (comp (ref "R5138")
      (value "*")
      (footprint "R0402")
      (description "НЁУГєсД¤µзЧи,0R,+/-5%,R0402,1/16W.")
      (fields
        (field (name "PCB FOOTPRINT") "R0402")
        (field (name "TOLERANCE") "5%")
        (field (name "OPTION") "DNP")
        (field (name "MANUFACTURER") "YAGEO")
        (field (name "ALTIUM_UNNAMED_1") "0R")
        (field (name "CREATED BY") "YTL")
      )
      (libsource (lib "*") (part "RESISTOR_Dup1"))
    )
    (comp (ref "R5139")
      (value "*")
      (footprint "R0402")
      (description "НЁУГєсД¤µзЧи,10K,+/-5%,R0402,1/16W.")
      (fields
        (field (name "PCB FOOTPRINT") "R0402")
        (field (name "TOLERANCE") "5%")
        (field (name "MANUFACTURER") "YAGEO")
        (field (name "OPTION") "DNP")
        (field (name "ALTIUM_UNNAMED_1") "10K")
        (field (name "CREATED BY") "YTL")
      )
      (libsource (lib "*") (part "RESISTOR_Dup1"))
    )
    (comp (ref "TP5100")
      (value "*")
      (footprint "TEST")
      (description "Test Point 0.7mm")
      (fields (field (name "ALTIUM_UNNAMED_1") "TP_0.7") (field (name "CREATED BY") "JJJ"))
      (libsource (lib "*") (part "TP"))
    )
    (comp (ref "TP5101")
      (value "*")
      (footprint "TEST")
      (description "Test Point 0.7mm")
      (fields (field (name "ALTIUM_UNNAMED_1") "TP_0.7") (field (name "CREATED BY") "JJJ"))
      (libsource (lib "*") (part "TP"))
    )
    (comp (ref "TP5102")
      (value "*")
      (footprint "TEST")
      (description "Test Point 0.7mm")
      (fields (field (name "ALTIUM_UNNAMED_1") "TP_0.7") (field (name "CREATED BY") "JJJ"))
      (libsource (lib "*") (part "TP"))
    )
    (comp (ref "U5100")
      (value "*")
      (footprint "QFN56_7R00X7R00X")
      (fields
        (field (name "PCB FOOTPRINT") "QFN56_7R00X7R00X0R90_T")
        (field (name "ALTIUM_UNNAMED_1") "IT6563FN")
      )
      (libsource (lib "*") (part "IT6563FN"))
    )
    (comp (ref "U5101")
      (value "*")
      (footprint "SOT_23_5")
      (description "High Efficiency 5.5V, 2A continuous, 3A peak, 1MHz Synchronous Step Down Regulator")
      (fields
        (field (name "PCB FOOTPRINT") "SOT_23_5")
        (field (name "MANUFACTURER") "SilergyЈЁОщБ¦ЅЬЈ©")
        (field (name "ALTIUM_UNNAMED_1") "ETA3409/SY8089AAC")
        (field (name "CREATED BY") "JJJ")
      )
      (libsource (lib "*") (part "DCDC_SY8088"))
    )
    (comp (ref "Y5100")
      (value "*")
      (footprint "CRY-3225")
      (description "ОЮФґѕ§ХсЈ¬27MЈ¬3225,ЎА10ppmЈ¬10pFЈ¬Hosonic")
      (fields
        (field (name "PCB FOOTPRINT") "CRY4_3R20X2R50X0R80")
        (field (name "MANUFACTURER") "Hosonic(єиРЗµзЧУ)")
        (field (name "ALTIUM_UNNAMED_1") "27MHz")
        (field (name "CREATED BY") "JJJ")
      )
      (libsource (lib "*") (part "CRYSTAL_4P"))
    )
  )
  (nets
    (net (code "1") (name "/DP1AUXN") (class "Default")
      (node (ref "C5100") (pin "2") (pinfunction "2_2") (pintype "passive"))
      (node (ref "U5100") (pin "26") (pinfunction "RXAUXN_26") (pintype "passive"))
    )
    (net (code "2") (name "/DP1AUXP") (class "Default")
      (node (ref "C5101") (pin "2") (pinfunction "2_2") (pintype "passive"))
      (node (ref "U5100") (pin "27") (pinfunction "RXAUXP_27") (pintype "passive"))
    )
    (net (code "3") (name "/DP2HDMI_RSTn") (class "Default")
      (node (ref "C5106") (pin "1") (pinfunction "1_1") (pintype "passive"))
      (node (ref "R5121") (pin "2") (pinfunction "2_2") (pintype "passive"))
      (node (ref "R5122") (pin "2") (pinfunction "2_2") (pintype "passive"))
      (node (ref "U5100") (pin "46") (pinfunction "SYSRSTN_46") (pintype "passive"))
    )
    (net (code "4") (name "/DP2HDMI_XIN") (class "Default")
      (node (ref "C5105") (pin "1") (pinfunction "1_1") (pintype "passive"))
      (node (ref "U5100") (pin "43") (pinfunction "XTALIN_43") (pintype "passive"))
      (node (ref "Y5100") (pin "3") (pinfunction "X2_3") (pintype "passive"))
    )
    (net (code "5") (name "/DP2HDMI_XOUT") (class "Default")
      (node (ref "R5115") (pin "2") (pinfunction "2_2") (pintype "passive"))
      (node (ref "U5100") (pin "42") (pinfunction "XTALOUT_42") (pintype "passive"))
    )
    (net (code "6") (name "/HDMI2_TX0N") (class "Default")
      (node (ref "R5109") (pin "1") (pinfunction "1_1") (pintype "passive"))
      (node (ref "U5100") (pin "8") (pinfunction "TX0M_8") (pintype "passive"))
    )
    (net (code "7") (name "/HDMI2_TX0N_PORT") (class "Default")
      (node (ref "ED5101") (pin "2") (pinfunction "IO2_2") (pintype "passive"))
      (node (ref "ED5101") (pin "9") (pinfunction "NC_9_9") (pintype "passive"))
      (node (ref "J5100") (pin "9") (pinfunction "D0N_9") (pintype "passive"))
      (node (ref "R5109") (pin "2") (pinfunction "2_2") (pintype "passive"))
    )
    (net (code "8") (name "/HDMI2_TX0P") (class "Default")
      (node (ref "R5108") (pin "1") (pinfunction "1_1") (pintype "passive"))
      (node (ref "U5100") (pin "9") (pinfunction "TX0P_9") (pintype "passive"))
    )
    (net (code "9") (name "/HDMI2_TX0P_PORT") (class "Default")
      (node (ref "ED5101") (pin "1") (pinfunction "IO1_1") (pintype "passive"))
      (node (ref "ED5101") (pin "10") (pinfunction "NC_10_10") (pintype "passive"))
      (node (ref "J5100") (pin "7") (pinfunction "D0P_7") (pintype "passive"))
      (node (ref "R5108") (pin "2") (pinfunction "2_2") (pintype "passive"))
    )
    (net (code "10") (name "/HDMI2_TX1N") (class "Default")
      (node (ref "R5106") (pin "1") (pinfunction "1_1") (pintype "passive"))
      (node (ref "U5100") (pin "11") (pinfunction "TX1M_11") (pintype "passive"))
    )
    (net (code "11") (name "/HDMI2_TX1N_PORT") (class "Default")
      (node (ref "ED5100") (pin "5") (pinfunction "IO4_5") (pintype "passive"))
      (node (ref "ED5100") (pin "6") (pinfunction "NC_6_6") (pintype "passive"))
      (node (ref "J5100") (pin "6") (pinfunction "D1N_6") (pintype "passive"))
      (node (ref "R5106") (pin "2") (pinfunction "2_2") (pintype "passive"))
    )
    (net (code "12") (name "/HDMI2_TX1P") (class "Default")
      (node (ref "R5105") (pin "1") (pinfunction "1_1") (pintype "passive"))
      (node (ref "U5100") (pin "12") (pinfunction "TX1P_12") (pintype "passive"))
    )
    (net (code "13") (name "/HDMI2_TX1P_PORT") (class "Default")
      (node (ref "ED5100") (pin "4") (pinfunction "IO3_4") (pintype "passive"))
      (node (ref "ED5100") (pin "7") (pinfunction "NC_7_7") (pintype "passive"))
      (node (ref "J5100") (pin "4") (pinfunction "D1P_4") (pintype "passive"))
      (node (ref "R5105") (pin "2") (pinfunction "2_2") (pintype "passive"))
    )
    (net (code "14") (name "/HDMI2_TX2N") (class "Default")
      (node (ref "R5104") (pin "1") (pinfunction "1_1") (pintype "passive"))
      (node (ref "U5100") (pin "13") (pinfunction "TX2M_13") (pintype "passive"))
    )
    (net (code "15") (name "/HDMI2_TX2N_PORT") (class "Default")
      (node (ref "ED5100") (pin "2") (pinfunction "IO2_2") (pintype "passive"))
      (node (ref "ED5100") (pin "9") (pinfunction "NC_9_9") (pintype "passive"))
      (node (ref "J5100") (pin "3") (pinfunction "D2N_3") (pintype "passive"))
      (node (ref "R5104") (pin "2") (pinfunction "2_2") (pintype "passive"))
    )
    (net (code "16") (name "/HDMI2_TX2P") (class "Default")
      (node (ref "R5103") (pin "1") (pinfunction "1_1") (pintype "passive"))
      (node (ref "U5100") (pin "14") (pinfunction "TX2P_14") (pintype "passive"))
    )
    (net (code "17") (name "/HDMI2_TX2P_PORT") (class "Default")
      (node (ref "ED5100") (pin "1") (pinfunction "IO1_1") (pintype "passive"))
      (node (ref "ED5100") (pin "10") (pinfunction "NC_10_10") (pintype "passive"))
      (node (ref "J5100") (pin "1") (pinfunction "D2P_1") (pintype "passive"))
      (node (ref "R5103") (pin "2") (pinfunction "2_2") (pintype "passive"))
    )
    (net (code "18") (name "/HDMI2_TXCN") (class "Default")
      (node (ref "C5103") (pin "2") (pinfunction "2_2") (pintype "passive"))
      (node (ref "L5100") (pin "4") (pinfunction "4_4") (pintype "passive"))
      (node (ref "R5111") (pin "1") (pinfunction "1_1") (pintype "passive"))
      (node (ref "U5100") (pin "6") (pinfunction "TXCM_6") (pintype "passive"))
    )
    (net (code "19") (name "/HDMI2_TXCN_PORT") (class "Default")
      (node (ref "ED5101") (pin "5") (pinfunction "IO4_5") (pintype "passive"))
      (node (ref "ED5101") (pin "6") (pinfunction "NC_6_6") (pintype "passive"))
      (node (ref "J5100") (pin "12") (pinfunction "CLKN_12") (pintype "passive"))
      (node (ref "L5100") (pin "3") (pinfunction "3_3") (pintype "passive"))
      (node (ref "R5111") (pin "2") (pinfunction "2_2") (pintype "passive"))
    )
    (net (code "20") (name "/HDMI2_TXCP") (class "Default")
      (node (ref "C5103") (pin "1") (pinfunction "1_1") (pintype "passive"))
      (node (ref "L5100") (pin "2") (pinfunction "2_2") (pintype "passive"))
      (node (ref "R5110") (pin "1") (pinfunction "1_1") (pintype "passive"))
      (node (ref "U5100") (pin "7") (pinfunction "TXCP_7") (pintype "passive"))
    )
    (net (code "21") (name "/HDMI2_TXCP_PORT") (class "Default")
      (node (ref "ED5101") (pin "4") (pinfunction "IO3_4") (pintype "passive"))
      (node (ref "ED5101") (pin "7") (pinfunction "NC_7_7") (pintype "passive"))
      (node (ref "J5100") (pin "10") (pinfunction "CLKP_10") (pintype "passive"))
      (node (ref "L5100") (pin "1") (pinfunction "1_1") (pintype "passive"))
      (node (ref "R5110") (pin "2") (pinfunction "2_2") (pintype "passive"))
    )
    (net (code "22") (name "/HDMI2_TX_CEC") (class "Default")
      (node (ref "R5116") (pin "1") (pinfunction "1_1") (pintype "passive"))
      (node (ref "R5136") (pin "1") (pinfunction "1_1") (pintype "passive"))
      (node (ref "U5100") (pin "2") (pinfunction "CEC_2") (pintype "passive"))
    )
    (net (code "23") (name "/HDMI2_TX_HPD") (class "Default")
      (node (ref "R5112") (pin "1") (pinfunction "1_1") (pintype "passive"))
      (node (ref "R5138") (pin "1") (pinfunction "1_1") (pintype "passive"))
      (node (ref "U5100") (pin "50") (pinfunction "HDMI_HPD_50") (pintype "passive"))
    )
    (net (code "24") (name "/HDMI2_TX_HPD_PORT") (class "Default")
      (node (ref "ED5102") (pin "1") (pinfunction "1_1") (pintype "passive"))
      (node (ref "J5100") (pin "19") (pinfunction "HPD_19") (pintype "passive"))
      (node (ref "R5112") (pin "2") (pinfunction "2_2") (pintype "passive"))
      (node (ref "R5114") (pin "1") (pinfunction "1_1") (pintype "passive"))
      (node (ref "R5137") (pin "2") (pinfunction "2_2") (pintype "passive"))
    )
    (net (code "25") (name "/HDMI2_TX_I2S0") (class "Default")
      (node (ref "R5118") (pin "1") (pinfunction "1_1") (pintype "passive"))
      (node (ref "U5100") (pin "55") (pinfunction "I2S0/SPDIF_55") (pintype "passive"))
    )
    (net (code "26") (name "/HDMI2_TX_SCL") (class "Default")
      (node (ref "R5102") (pin "2") (pinfunction "2_2") (pintype "passive"))
      (node (ref "R5124") (pin "1") (pinfunction "1_1") (pintype "passive"))
      (node (ref "U5100") (pin "52") (pinfunction "DDCSCL_52") (pintype "passive"))
    )
    (net (code "27") (name "/HDMI2_TX_SCL_PORT") (class "Default")
      (node (ref "ED5104") (pin "1") (pinfunction "1_1") (pintype "passive"))
      (node (ref "J5100") (pin "15") (pinfunction "SCL_15") (pintype "passive"))
      (node (ref "R5123") (pin "2") (pinfunction "2_2") (pintype "passive"))
      (node (ref "R5124") (pin "2") (pinfunction "2_2") (pintype "passive"))
    )
    (net (code "28") (name "/HDMI2_TX_SDA") (class "Default")
      (node (ref "R5107") (pin "2") (pinfunction "2_2") (pintype "passive"))
      (node (ref "R5127") (pin "1") (pinfunction "1_1") (pintype "passive"))
      (node (ref "U5100") (pin "51") (pinfunction "DDCSDA_51") (pintype "passive"))
    )
    (net (code "29") (name "/HDMI2_TX_SDA_PORT") (class "Default")
      (node (ref "ED5103") (pin "1") (pinfunction "1_1") (pintype "passive"))
      (node (ref "J5100") (pin "16") (pinfunction "SDA_16") (pintype "passive"))
      (node (ref "R5125") (pin "2") (pinfunction "2_2") (pintype "passive"))
      (node (ref "R5127") (pin "2") (pinfunction "2_2") (pintype "passive"))
    )
    (net (code "30") (name "/HDMI2_TX_WS") (class "Default")
      (node (ref "R5119") (pin "1") (pinfunction "1_1") (pintype "passive"))
      (node (ref "U5100") (pin "56") (pinfunction "WS_56") (pintype "passive"))
    )
    (net (code "31") (name "DP1_AUXN") (class "Default")
      (node (ref "C5100") (pin "1") (pinfunction "1_1") (pintype "passive"))
    )
    (net (code "32") (name "DP1_AUXP") (class "Default")
      (node (ref "C5101") (pin "1") (pinfunction "1_1") (pintype "passive"))
    )
    (net (code "33") (name "DP1_HPDIN_M2") (class "Default")
      (node (ref "D5102") (pin "1") (pinfunction "A_1") (pintype "passive"))
      (node (ref "R5100") (pin "1") (pinfunction "1_1") (pintype "passive"))
      (node (ref "R5101") (pin "1") (pinfunction "1_1") (pintype "passive"))
      (node (ref "R5135") (pin "2") (pinfunction "2_2") (pintype "passive"))
    )
    (net (code "34") (name "DP1_TX0N") (class "Default")
      (node (ref "U5100") (pin "30") (pinfunction "RX0N_30") (pintype "passive"))
    )
    (net (code "35") (name "DP1_TX0P") (class "Default")
      (node (ref "U5100") (pin "29") (pinfunction "RX0P_29") (pintype "passive"))
    )
    (net (code "36") (name "DP1_TX1N") (class "Default")
      (node (ref "U5100") (pin "33") (pinfunction "RX1N_33") (pintype "passive"))
    )
    (net (code "37") (name "DP1_TX1P") (class "Default")
      (node (ref "U5100") (pin "32") (pinfunction "RX1P_32") (pintype "passive"))
    )
    (net (code "38") (name "DP1_TX2N") (class "Default")
      (node (ref "U5100") (pin "35") (pinfunction "RX2N_35") (pintype "passive"))
    )
    (net (code "39") (name "DP1_TX2P") (class "Default")
      (node (ref "U5100") (pin "34") (pinfunction "RX2P_34") (pintype "passive"))
    )
    (net (code "40") (name "DP1_TX3N") (class "Default")
      (node (ref "U5100") (pin "38") (pinfunction "RX3N_38") (pintype "passive"))
    )
    (net (code "41") (name "DP1_TX3P") (class "Default")
      (node (ref "U5100") (pin "37") (pinfunction "RX3P_37") (pintype "passive"))
    )
    (net (code "42") (name "DP2HDMI_PWREN_H_GPIO3_B2") (class "Default")
      (node (ref "R5129") (pin "1") (pinfunction "1_1") (pintype "passive"))
      (node (ref "R5131") (pin "1") (pinfunction "1_1") (pintype "passive"))
    )
    (net (code "43") (name "DP2HDMI_RSTn_GPIO0_D5") (class "Default")
      (node (ref "R5122") (pin "1") (pinfunction "1_1") (pintype "passive"))
    )
    (net (code "44") (name "GND") (class "Default")
      (node (ref "C5102") (pin "2") (pinfunction "2_2") (pintype "passive"))
      (node (ref "C5104") (pin "2") (pinfunction "2_2") (pintype "passive"))
      (node (ref "C5105") (pin "2") (pinfunction "2_2") (pintype "passive"))
      (node (ref "C5106") (pin "2") (pinfunction "2_2") (pintype "passive"))
      (node (ref "C5107") (pin "2") (pinfunction "2_2") (pintype "passive"))
      (node (ref "C5109") (pin "2") (pinfunction "2_2") (pintype "passive"))
      (node (ref "C5110") (pin "2") (pinfunction "2_2") (pintype "passive"))
      (node (ref "C5111") (pin "2") (pinfunction "2_2") (pintype "passive"))
      (node (ref "C5112") (pin "2") (pinfunction "2_2") (pintype "passive"))
      (node (ref "C5113") (pin "2") (pinfunction "2_2") (pintype "passive"))
      (node (ref "C5114") (pin "2") (pinfunction "2_2") (pintype "passive"))
      (node (ref "C5115") (pin "2") (pinfunction "2_2") (pintype "passive"))
      (node (ref "C5116") (pin "2") (pinfunction "2_2") (pintype "passive"))
      (node (ref "C5117") (pin "2") (pinfunction "2_2") (pintype "passive"))
      (node (ref "C5118") (pin "2") (pinfunction "2_2") (pintype "passive"))
      (node (ref "C5119") (pin "2") (pinfunction "2_2") (pintype "passive"))
      (node (ref "C5121") (pin "2") (pinfunction "2_2") (pintype "passive"))
      (node (ref "C5122") (pin "2") (pinfunction "2_2") (pintype "passive"))
      (node (ref "C5123") (pin "2") (pinfunction "2_2") (pintype "passive"))
      (node (ref "C5124") (pin "2") (pinfunction "2_2") (pintype "passive"))
      (node (ref "C5125") (pin "2") (pinfunction "2_2") (pintype "passive"))
      (node (ref "C5126") (pin "2") (pinfunction "2_2") (pintype "passive"))
      (node (ref "C5127") (pin "2") (pinfunction "2_2") (pintype "passive"))
      (node (ref "C5128") (pin "2") (pinfunction "2_2") (pintype "passive"))
      (node (ref "C5129") (pin "2") (pinfunction "2_2") (pintype "passive"))
      (node (ref "C5130") (pin "2") (pinfunction "2_2") (pintype "passive"))
      (node (ref "C5131") (pin "2") (pinfunction "2_2") (pintype "passive"))
      (node (ref "C5132") (pin "2") (pinfunction "2_2") (pintype "passive"))
      (node (ref "C5133") (pin "2") (pinfunction "2_2") (pintype "passive"))
      (node (ref "C5134") (pin "2") (pinfunction "2_2") (pintype "passive"))
      (node (ref "C5135") (pin "2") (pinfunction "2_2") (pintype "passive"))
      (node (ref "C5136") (pin "2") (pinfunction "2_2") (pintype "passive"))
      (node (ref "C5137") (pin "2") (pinfunction "2_2") (pintype "passive"))
      (node (ref "C5138") (pin "2") (pinfunction "2_2") (pintype "passive"))
      (node (ref "C5139") (pin "2") (pinfunction "2_2") (pintype "passive"))
      (node (ref "C5140") (pin "2") (pinfunction "2_2") (pintype "passive"))
      (node (ref "C5141") (pin "2") (pinfunction "2_2") (pintype "passive"))
      (node (ref "C5142") (pin "2") (pinfunction "2_2") (pintype "passive"))
      (node (ref "ED5100") (pin "3") (pinfunction "GND_3") (pintype "power_in"))
      (node (ref "ED5100") (pin "8") (pinfunction "GND_8") (pintype "power_in"))
      (node (ref "ED5101") (pin "3") (pinfunction "GND_3") (pintype "power_in"))
      (node (ref "ED5101") (pin "8") (pinfunction "GND_8") (pintype "power_in"))
      (node (ref "ED5102") (pin "2") (pinfunction "2_2") (pintype "passive"))
      (node (ref "ED5103") (pin "2") (pinfunction "2_2") (pintype "passive"))
      (node (ref "ED5104") (pin "2") (pinfunction "2_2") (pintype "passive"))
      (node (ref "J5100") (pin "11") (pinfunction "CLK_G_11") (pintype "passive"))
      (node (ref "J5100") (pin "17") (pinfunction "GND_17") (pintype "passive"))
      (node (ref "J5100") (pin "2") (pinfunction "D2_G_2") (pintype "passive"))
      (node (ref "J5100") (pin "20") (pinfunction "G1_20") (pintype "passive"))
      (node (ref "J5100") (pin "21") (pinfunction "G2_21") (pintype "passive"))
      (node (ref "J5100") (pin "22") (pinfunction "G3_22") (pintype "passive"))
      (node (ref "J5100") (pin "23") (pinfunction "G4_23") (pintype "passive"))
      (node (ref "J5100") (pin "5") (pinfunction "D1_G_5") (pintype "passive"))
      (node (ref "J5100") (pin "8") (pinfunction "D0_G_8") (pintype "passive"))
      (node (ref "Q5101") (pin "2") (pinfunction "EMITTER_2") (pintype "passive"))
      (node (ref "R5100") (pin "2") (pinfunction "2_2") (pintype "passive"))
      (node (ref "R5113") (pin "2") (pinfunction "2_2") (pintype "passive"))
      (node (ref "R5114") (pin "2") (pinfunction "2_2") (pintype "passive"))
      (node (ref "R5116") (pin "2") (pinfunction "2_2") (pintype "passive"))
      (node (ref "R5117") (pin "2") (pinfunction "2_2") (pintype "passive"))
      (node (ref "R5118") (pin "2") (pinfunction "2_2") (pintype "passive"))
      (node (ref "R5119") (pin "2") (pinfunction "2_2") (pintype "passive"))
      (node (ref "R5130") (pin "2") (pinfunction "2_2") (pintype "passive"))
      (node (ref "R5133") (pin "2") (pinfunction "2_2") (pintype "passive"))
      (node (ref "R5139") (pin "2") (pinfunction "2_2") (pintype "passive"))
      (node (ref "U5100") (pin "57") (pinfunction "EPAD_57") (pintype "passive"))
      (node (ref "U5101") (pin "2") (pinfunction "GND_2") (pintype "passive"))
      (node (ref "Y5100") (pin "2") (pinfunction "GND_2") (pintype "power_in"))
      (node (ref "Y5100") (pin "4") (pinfunction "GND_4") (pintype "power_in"))
    )
    (net (code "45") (name "Net-(D5101-K)") (class "Default")
      (node (ref "D5101") (pin "2") (pinfunction "K_2") (pintype "passive"))
      (node (ref "R5123") (pin "1") (pinfunction "1_1") (pintype "passive"))
      (node (ref "R5125") (pin "1") (pinfunction "1_1") (pintype "passive"))
    )
    (net (code "46") (name "Net-(D5102-K)") (class "Default")
      (node (ref "D5102") (pin "2") (pinfunction "K_2") (pintype "passive"))
      (node (ref "R5137") (pin "1") (pinfunction "1_1") (pintype "passive"))
      (node (ref "R5139") (pin "1") (pinfunction "1_1") (pintype "passive"))
    )
    (net (code "47") (name "Net-(Q5100-GATE)") (class "Default")
      (node (ref "C5108") (pin "2") (pinfunction "2_2") (pintype "passive"))
      (node (ref "Q5100") (pin "1") (pinfunction "GATE_1") (pintype "passive"))
      (node (ref "R5126") (pin "2") (pinfunction "2_2") (pintype "passive"))
      (node (ref "R5128") (pin "1") (pinfunction "1_1") (pintype "passive"))
    )
    (net (code "48") (name "Net-(Q5101-BASE)") (class "Default")
      (node (ref "C5114") (pin "1") (pinfunction "1_1") (pintype "passive"))
      (node (ref "Q5101") (pin "1") (pinfunction "BASE_1") (pintype "passive"))
      (node (ref "R5129") (pin "2") (pinfunction "2_2") (pintype "passive"))
      (node (ref "R5130") (pin "1") (pinfunction "1_1") (pintype "passive"))
    )
    (net (code "49") (name "Net-(Q5101-COLLECTOR)") (class "Default")
      (node (ref "Q5101") (pin "3") (pinfunction "COLLECTOR_3") (pintype "passive"))
      (node (ref "R5128") (pin "2") (pinfunction "2_2") (pintype "passive"))
    )
    (net (code "50") (name "Net-(U5100-DP_HPD)") (class "Default")
      (node (ref "R5101") (pin "2") (pinfunction "2_2") (pintype "passive"))
      (node (ref "U5100") (pin "22") (pinfunction "DP_HPD_22") (pintype "passive"))
    )
    (net (code "51") (name "Net-(U5100-HWTRAPN)") (class "Default")
      (node (ref "TP5100") (pin "1") (pinfunction "1_1") (pintype "passive"))
      (node (ref "U5100") (pin "49") (pinfunction "HWTRAPN_49") (pintype "passive"))
    )
    (net (code "52") (name "Net-(U5100-ISPSCL)") (class "Default")
      (node (ref "R5102") (pin "1") (pinfunction "1_1") (pintype "passive"))
      (node (ref "U5100") (pin "18") (pinfunction "ISPSCL_18") (pintype "passive"))
    )
    (net (code "53") (name "Net-(U5100-ISPSDA)") (class "Default")
      (node (ref "R5107") (pin "1") (pinfunction "1_1") (pintype "passive"))
      (node (ref "U5100") (pin "19") (pinfunction "ISPSDA_19") (pintype "passive"))
    )
    (net (code "54") (name "Net-(U5100-PCSCL)") (class "Default")
      (node (ref "TP5101") (pin "1") (pinfunction "1_1") (pintype "passive"))
      (node (ref "U5100") (pin "48") (pinfunction "PCSCL_48") (pintype "passive"))
    )
    (net (code "55") (name "Net-(U5100-PCSDA)") (class "Default")
      (node (ref "TP5102") (pin "1") (pinfunction "1_1") (pintype "passive"))
      (node (ref "U5100") (pin "47") (pinfunction "PCSDA_47") (pintype "passive"))
    )
    (net (code "56") (name "Net-(U5100-REXT)") (class "Default")
      (node (ref "R5113") (pin "1") (pinfunction "1_1") (pintype "passive"))
      (node (ref "U5100") (pin "5") (pinfunction "REXT_5") (pintype "passive"))
    )
    (net (code "57") (name "Net-(U5100-URDBG)") (class "Default")
      (node (ref "R5117") (pin "1") (pinfunction "1_1") (pintype "passive"))
      (node (ref "U5100") (pin "45") (pinfunction "URDBG_45") (pintype "passive"))
    )
    (net (code "58") (name "Net-(U5101-EN)") (class "Default")
      (node (ref "C5134") (pin "1") (pinfunction "1_1") (pintype "passive"))
      (node (ref "R5131") (pin "2") (pinfunction "2_2") (pintype "passive"))
      (node (ref "U5101") (pin "1") (pinfunction "EN_1") (pintype "passive"))
    )
    (net (code "59") (name "Net-(U5101-FB{slash}OUT)") (class "Default")
      (node (ref "C5120") (pin "2") (pinfunction "2_2") (pintype "passive"))
      (node (ref "R5132") (pin "2") (pinfunction "2_2") (pintype "passive"))
      (node (ref "R5133") (pin "1") (pinfunction "1_1") (pintype "passive"))
      (node (ref "U5101") (pin "5") (pinfunction "FB/OUT_5") (pintype "passive"))
    )
    (net (code "60") (name "Net-(U5101-LX)") (class "Default")
      (node (ref "L5101") (pin "1") (pinfunction "1_1") (pintype "passive"))
      (node (ref "U5101") (pin "3") (pinfunction "LX_3") (pintype "passive"))
    )
    (net (code "61") (name "Net-(Y5100-X1)") (class "Default")
      (node (ref "C5104") (pin "1") (pinfunction "1_1") (pintype "passive"))
      (node (ref "R5115") (pin "1") (pinfunction "1_1") (pintype "passive"))
      (node (ref "Y5100") (pin "1") (pinfunction "X1_1") (pintype "passive"))
    )
    (net (code "62") (name "VCC4V0_SYS") (class "Default")
      (node (ref "C5119") (pin "1") (pinfunction "1_1") (pintype "passive"))
      (node (ref "U5101") (pin "4") (pinfunction "VIN_4") (pintype "passive"))
    )
    (net (code "63") (name "VCC5V0_SYS") (class "Default")
      (node (ref "D5100") (pin "1") (pinfunction "A_1") (pintype "passive"))
      (node (ref "D5101") (pin "1") (pinfunction "A_1") (pintype "passive"))
      (node (ref "R5120") (pin "1") (pinfunction "1_1") (pintype "passive"))
    )
    (net (code "64") (name "VCC5V_HDMI_TX2") (class "Default")
      (node (ref "C5102") (pin "1") (pinfunction "1_1") (pintype "passive"))
      (node (ref "D5100") (pin "2") (pinfunction "K_2") (pintype "passive"))
      (node (ref "J5100") (pin "18") (pinfunction "+5V_18") (pintype "passive"))
      (node (ref "R5120") (pin "2") (pinfunction "2_2") (pintype "passive"))
    )
    (net (code "65") (name "VCCA_ASPVCC33") (class "Default")
      (node (ref "C5115") (pin "1") (pinfunction "1_1") (pintype "passive"))
      (node (ref "C5116") (pin "1") (pinfunction "1_1") (pintype "passive"))
      (node (ref "C5117") (pin "1") (pinfunction "1_1") (pintype "passive"))
      (node (ref "C5118") (pin "1") (pinfunction "1_1") (pintype "passive"))
      (node (ref "FB5101") (pin "2") (pinfunction "2_2") (pintype "passive"))
      (node (ref "U5100") (pin "24") (pinfunction "RXPVCC33_24") (pintype "passive"))
      (node (ref "U5100") (pin "39") (pinfunction "RXAVDD33_39") (pintype "passive"))
      (node (ref "U5100") (pin "40") (pinfunction "ASPVCC33_40") (pintype "passive"))
    )
    (net (code "66") (name "VCCA_TPVCC33") (class "Default")
      (node (ref "C5110") (pin "1") (pinfunction "1_1") (pintype "passive"))
      (node (ref "C5111") (pin "1") (pinfunction "1_1") (pintype "passive"))
      (node (ref "FB5100") (pin "2") (pinfunction "2_2") (pintype "passive"))
      (node (ref "U5100") (pin "3") (pinfunction "TPVCC33_3") (pintype "passive"))
    )
    (net (code "67") (name "VCC_1V8") (class "Default")
      (node (ref "R5135") (pin "1") (pinfunction "1_1") (pintype "passive"))
    )
    (net (code "68") (name "VCC_3V3") (class "Default")
      (node (ref "C5107") (pin "1") (pinfunction "1_1") (pintype "passive"))
      (node (ref "C5108") (pin "1") (pinfunction "1_1") (pintype "passive"))
      (node (ref "Q5100") (pin "2") (pinfunction "SOURCE_2") (pintype "passive"))
      (node (ref "R5126") (pin "1") (pinfunction "1_1") (pintype "passive"))
    )
    (net (code "69") (name "VCC_OVDD33") (class "Default")
      (node (ref "C5109") (pin "1") (pinfunction "1_1") (pintype "passive"))
      (node (ref "C5112") (pin "1") (pinfunction "1_1") (pintype "passive"))
      (node (ref "C5113") (pin "1") (pinfunction "1_1") (pintype "passive"))
      (node (ref "FB5100") (pin "1") (pinfunction "1_1") (pintype "passive"))
      (node (ref "FB5101") (pin "1") (pinfunction "1_1") (pintype "passive"))
      (node (ref "Q5100") (pin "3") (pinfunction "DRAIN_3") (pintype "passive"))
      (node (ref "R5121") (pin "1") (pinfunction "1_1") (pintype "passive"))
      (node (ref "R5136") (pin "2") (pinfunction "2_2") (pintype "passive"))
      (node (ref "R5138") (pin "2") (pinfunction "2_2") (pintype "passive"))
      (node (ref "U5100") (pin "20") (pinfunction "OVDD33_20_20") (pintype "passive"))
      (node (ref "U5100") (pin "23") (pinfunction "OVDD33_23_23") (pintype "passive"))
      (node (ref "U5100") (pin "53") (pinfunction "OVDD33_53_53") (pintype "passive"))
    )
    (net (code "70") (name "VDD_ASPVCC10") (class "Default")
      (node (ref "C5127") (pin "1") (pinfunction "1_1") (pintype "passive"))
      (node (ref "C5128") (pin "1") (pinfunction "1_1") (pintype "passive"))
      (node (ref "C5129") (pin "1") (pinfunction "1_1") (pintype "passive"))
      (node (ref "C5130") (pin "1") (pinfunction "1_1") (pintype "passive"))
      (node (ref "C5131") (pin "1") (pinfunction "1_1") (pintype "passive"))
      (node (ref "C5132") (pin "1") (pinfunction "1_1") (pintype "passive"))
      (node (ref "C5133") (pin "1") (pinfunction "1_1") (pintype "passive"))
      (node (ref "FB5102") (pin "2") (pinfunction "2_2") (pintype "passive"))
      (node (ref "U5100") (pin "25") (pinfunction "RXPVCC10_25") (pintype "passive"))
      (node (ref "U5100") (pin "31") (pinfunction "RXAVDD10_31_31") (pintype "passive"))
      (node (ref "U5100") (pin "36") (pinfunction "RXAVDD10_36_36") (pintype "passive"))
      (node (ref "U5100") (pin "41") (pinfunction "ASPVCC10_41") (pintype "passive"))
    )
    (net (code "71") (name "VDD_IVDD10") (class "Default")
      (node (ref "C5120") (pin "1") (pinfunction "1_1") (pintype "passive"))
      (node (ref "C5121") (pin "1") (pinfunction "1_1") (pintype "passive"))
      (node (ref "C5122") (pin "1") (pinfunction "1_1") (pintype "passive"))
      (node (ref "C5123") (pin "1") (pinfunction "1_1") (pintype "passive"))
      (node (ref "C5124") (pin "1") (pinfunction "1_1") (pintype "passive"))
      (node (ref "C5125") (pin "1") (pinfunction "1_1") (pintype "passive"))
      (node (ref "C5126") (pin "1") (pinfunction "1_1") (pintype "passive"))
      (node (ref "C5135") (pin "1") (pinfunction "1_1") (pintype "passive"))
      (node (ref "C5136") (pin "1") (pinfunction "1_1") (pintype "passive"))
      (node (ref "C5137") (pin "1") (pinfunction "1_1") (pintype "passive"))
      (node (ref "C5138") (pin "1") (pinfunction "1_1") (pintype "passive"))
      (node (ref "FB5102") (pin "1") (pinfunction "1_1") (pintype "passive"))
      (node (ref "FB5103") (pin "1") (pinfunction "1_1") (pintype "passive"))
      (node (ref "L5101") (pin "2") (pinfunction "2_2") (pintype "passive"))
      (node (ref "R5132") (pin "1") (pinfunction "1_1") (pintype "passive"))
      (node (ref "U5100") (pin "15") (pinfunction "TDVDD10_15") (pintype "passive"))
      (node (ref "U5100") (pin "17") (pinfunction "IVDD10_17_17") (pintype "passive"))
      (node (ref "U5100") (pin "21") (pinfunction "IVDD10_21_21") (pintype "passive"))
      (node (ref "U5100") (pin "28") (pinfunction "RXDVDD10_28") (pintype "passive"))
      (node (ref "U5100") (pin "44") (pinfunction "IVDD10_44") (pintype "passive"))
      (node (ref "U5100") (pin "54") (pinfunction "IVDD10_54_54") (pintype "passive"))
    )
    (net (code "72") (name "VDD_TAVCC10") (class "Default")
      (node (ref "C5139") (pin "1") (pinfunction "1_1") (pintype "passive"))
      (node (ref "C5140") (pin "1") (pinfunction "1_1") (pintype "passive"))
      (node (ref "C5141") (pin "1") (pinfunction "1_1") (pintype "passive"))
      (node (ref "C5142") (pin "1") (pinfunction "1_1") (pintype "passive"))
      (node (ref "FB5103") (pin "2") (pinfunction "2_2") (pintype "passive"))
      (node (ref "U5100") (pin "10") (pinfunction "TAVCC10_10") (pintype "passive"))
      (node (ref "U5100") (pin "4") (pinfunction "TPVCC10_4") (pintype "passive"))
    )
    (net (code "73") (name "unconnected-(J5100-CEC-Pad13)") (class "Default")
      (node (ref "J5100") (pin "13") (pinfunction "CEC_13") (pintype "passive+no_connect"))
    )
    (net (code "74") (name "unconnected-(J5100-Utility-Pad14)") (class "Default")
      (node (ref "J5100") (pin "14") (pinfunction "Utility_14") (pintype "passive+no_connect"))
    )
    (net (code "75") (name "unconnected-(U5100-NC-Pad16)") (class "Default")
      (node (ref "U5100") (pin "16") (pinfunction "NC_16") (pintype "passive+no_connect"))
    )
    (net (code "76") (name "unconnected-(U5100-SCK{slash}MCLK-Pad1)") (class "Default")
      (node (ref "U5100") (pin "1") (pinfunction "SCK/MCLK_1") (pintype "passive+no_connect"))
    )
  )
)
